# VistelV3.net
KiCad netlist of a schematic drawn in EAGLE
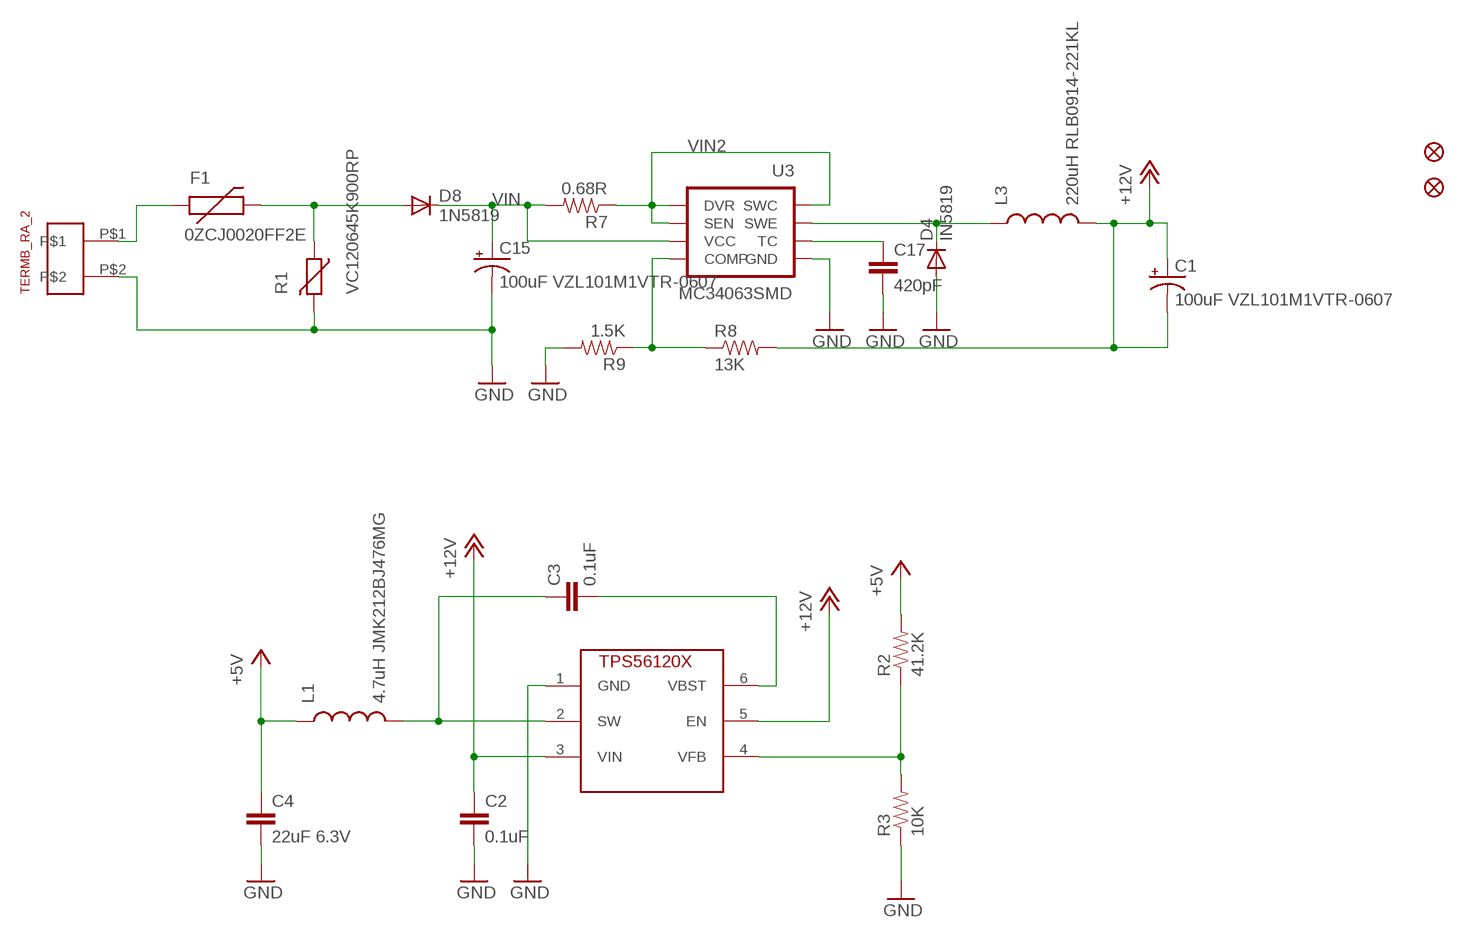
[diagram p0: schematic, sheet 1]
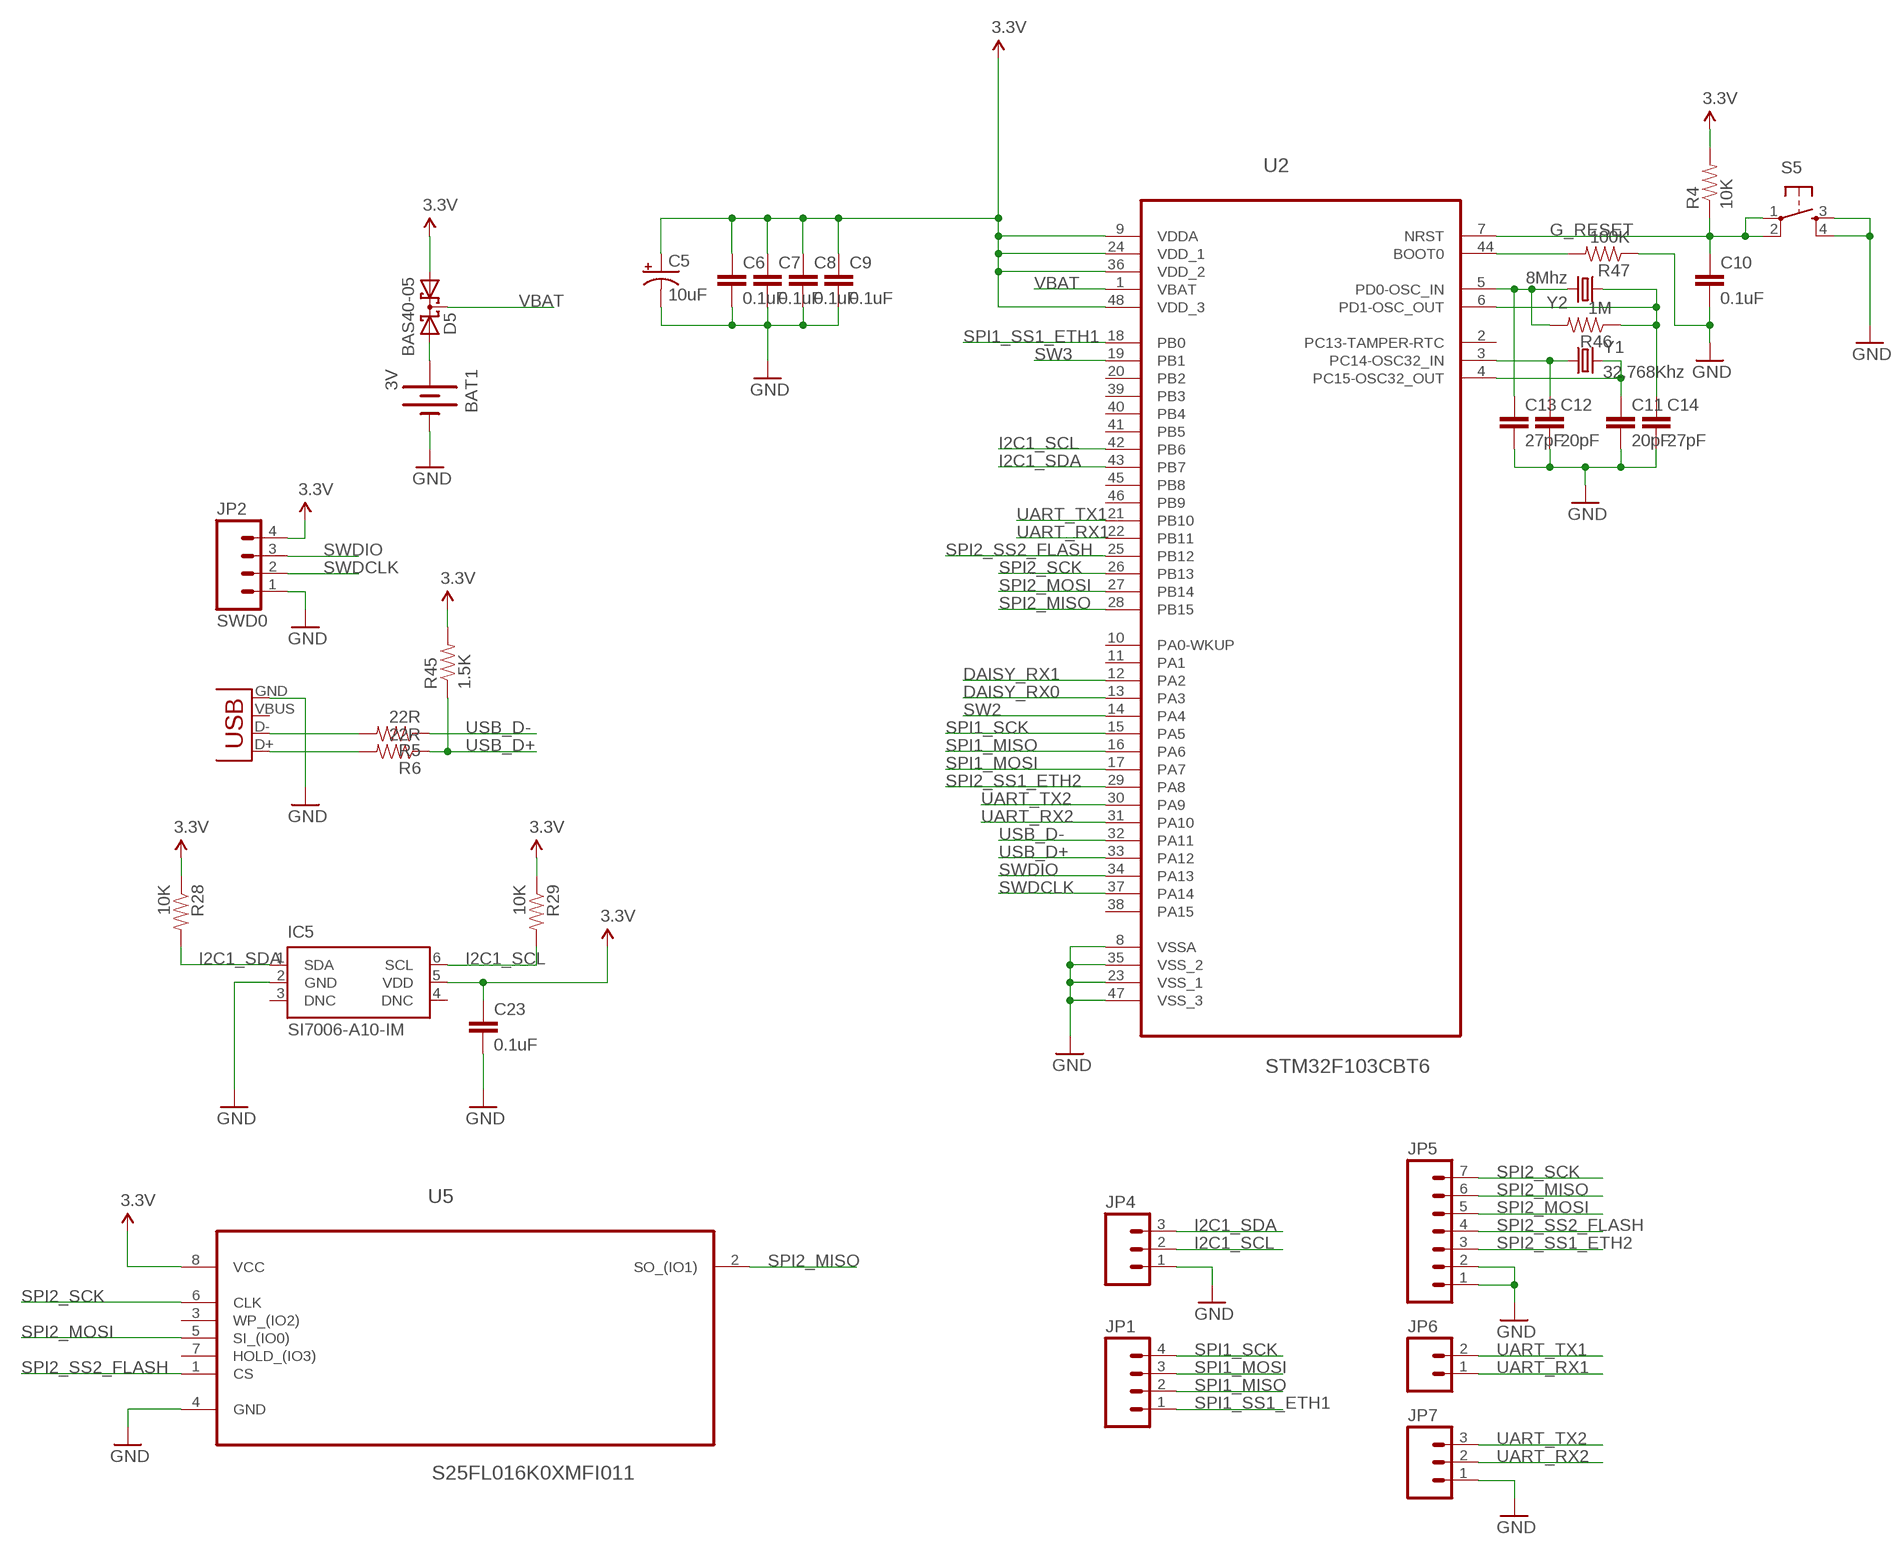
[diagram p1: schematic, sheet 2]
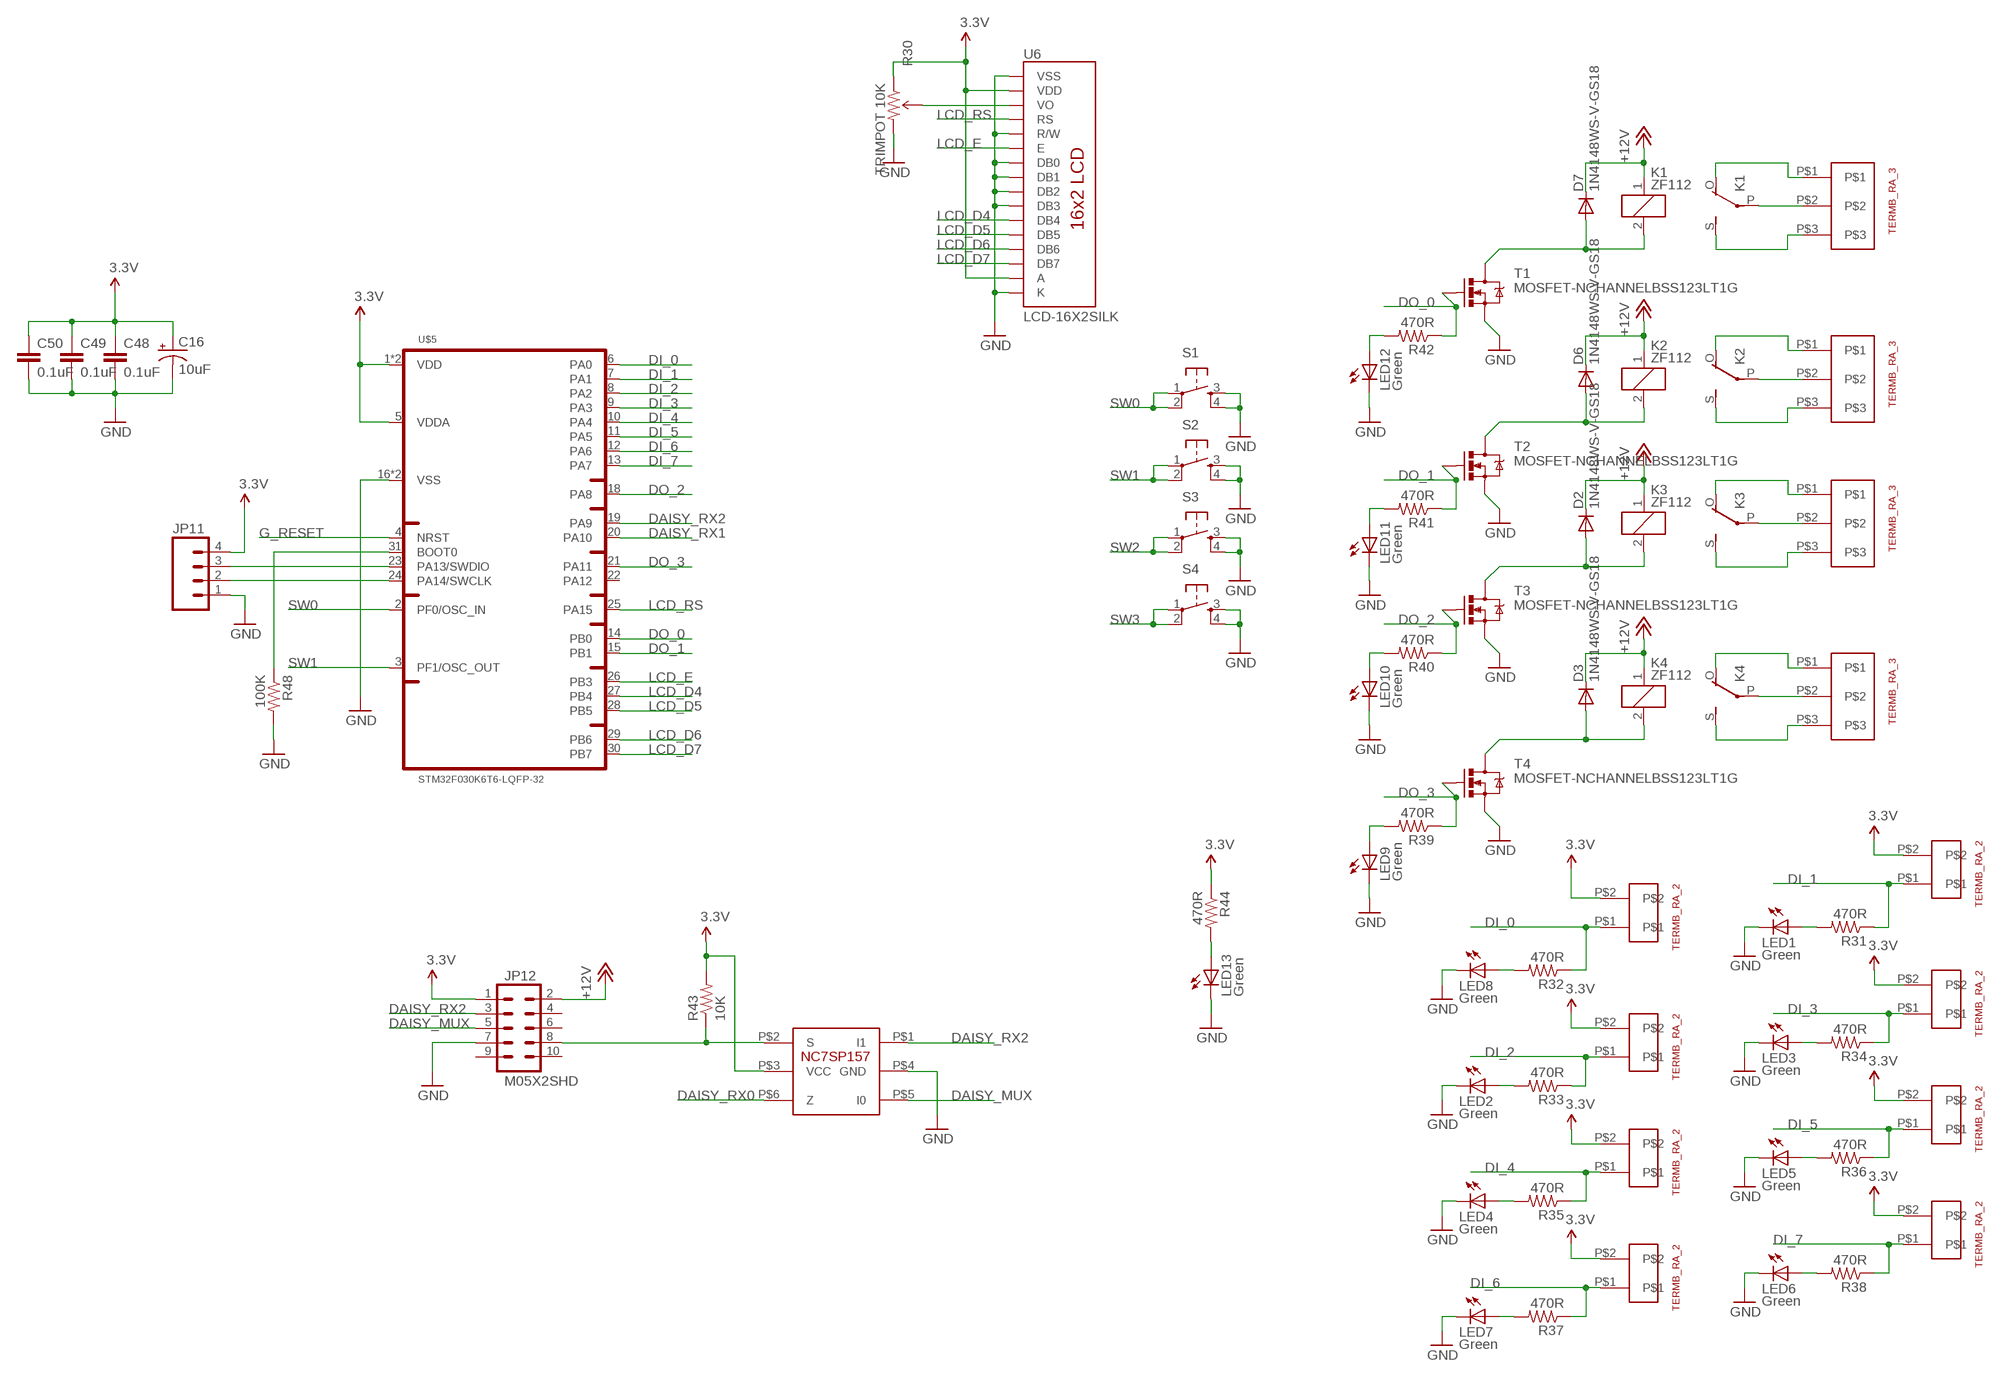
[diagram p2: schematic, sheet 3]
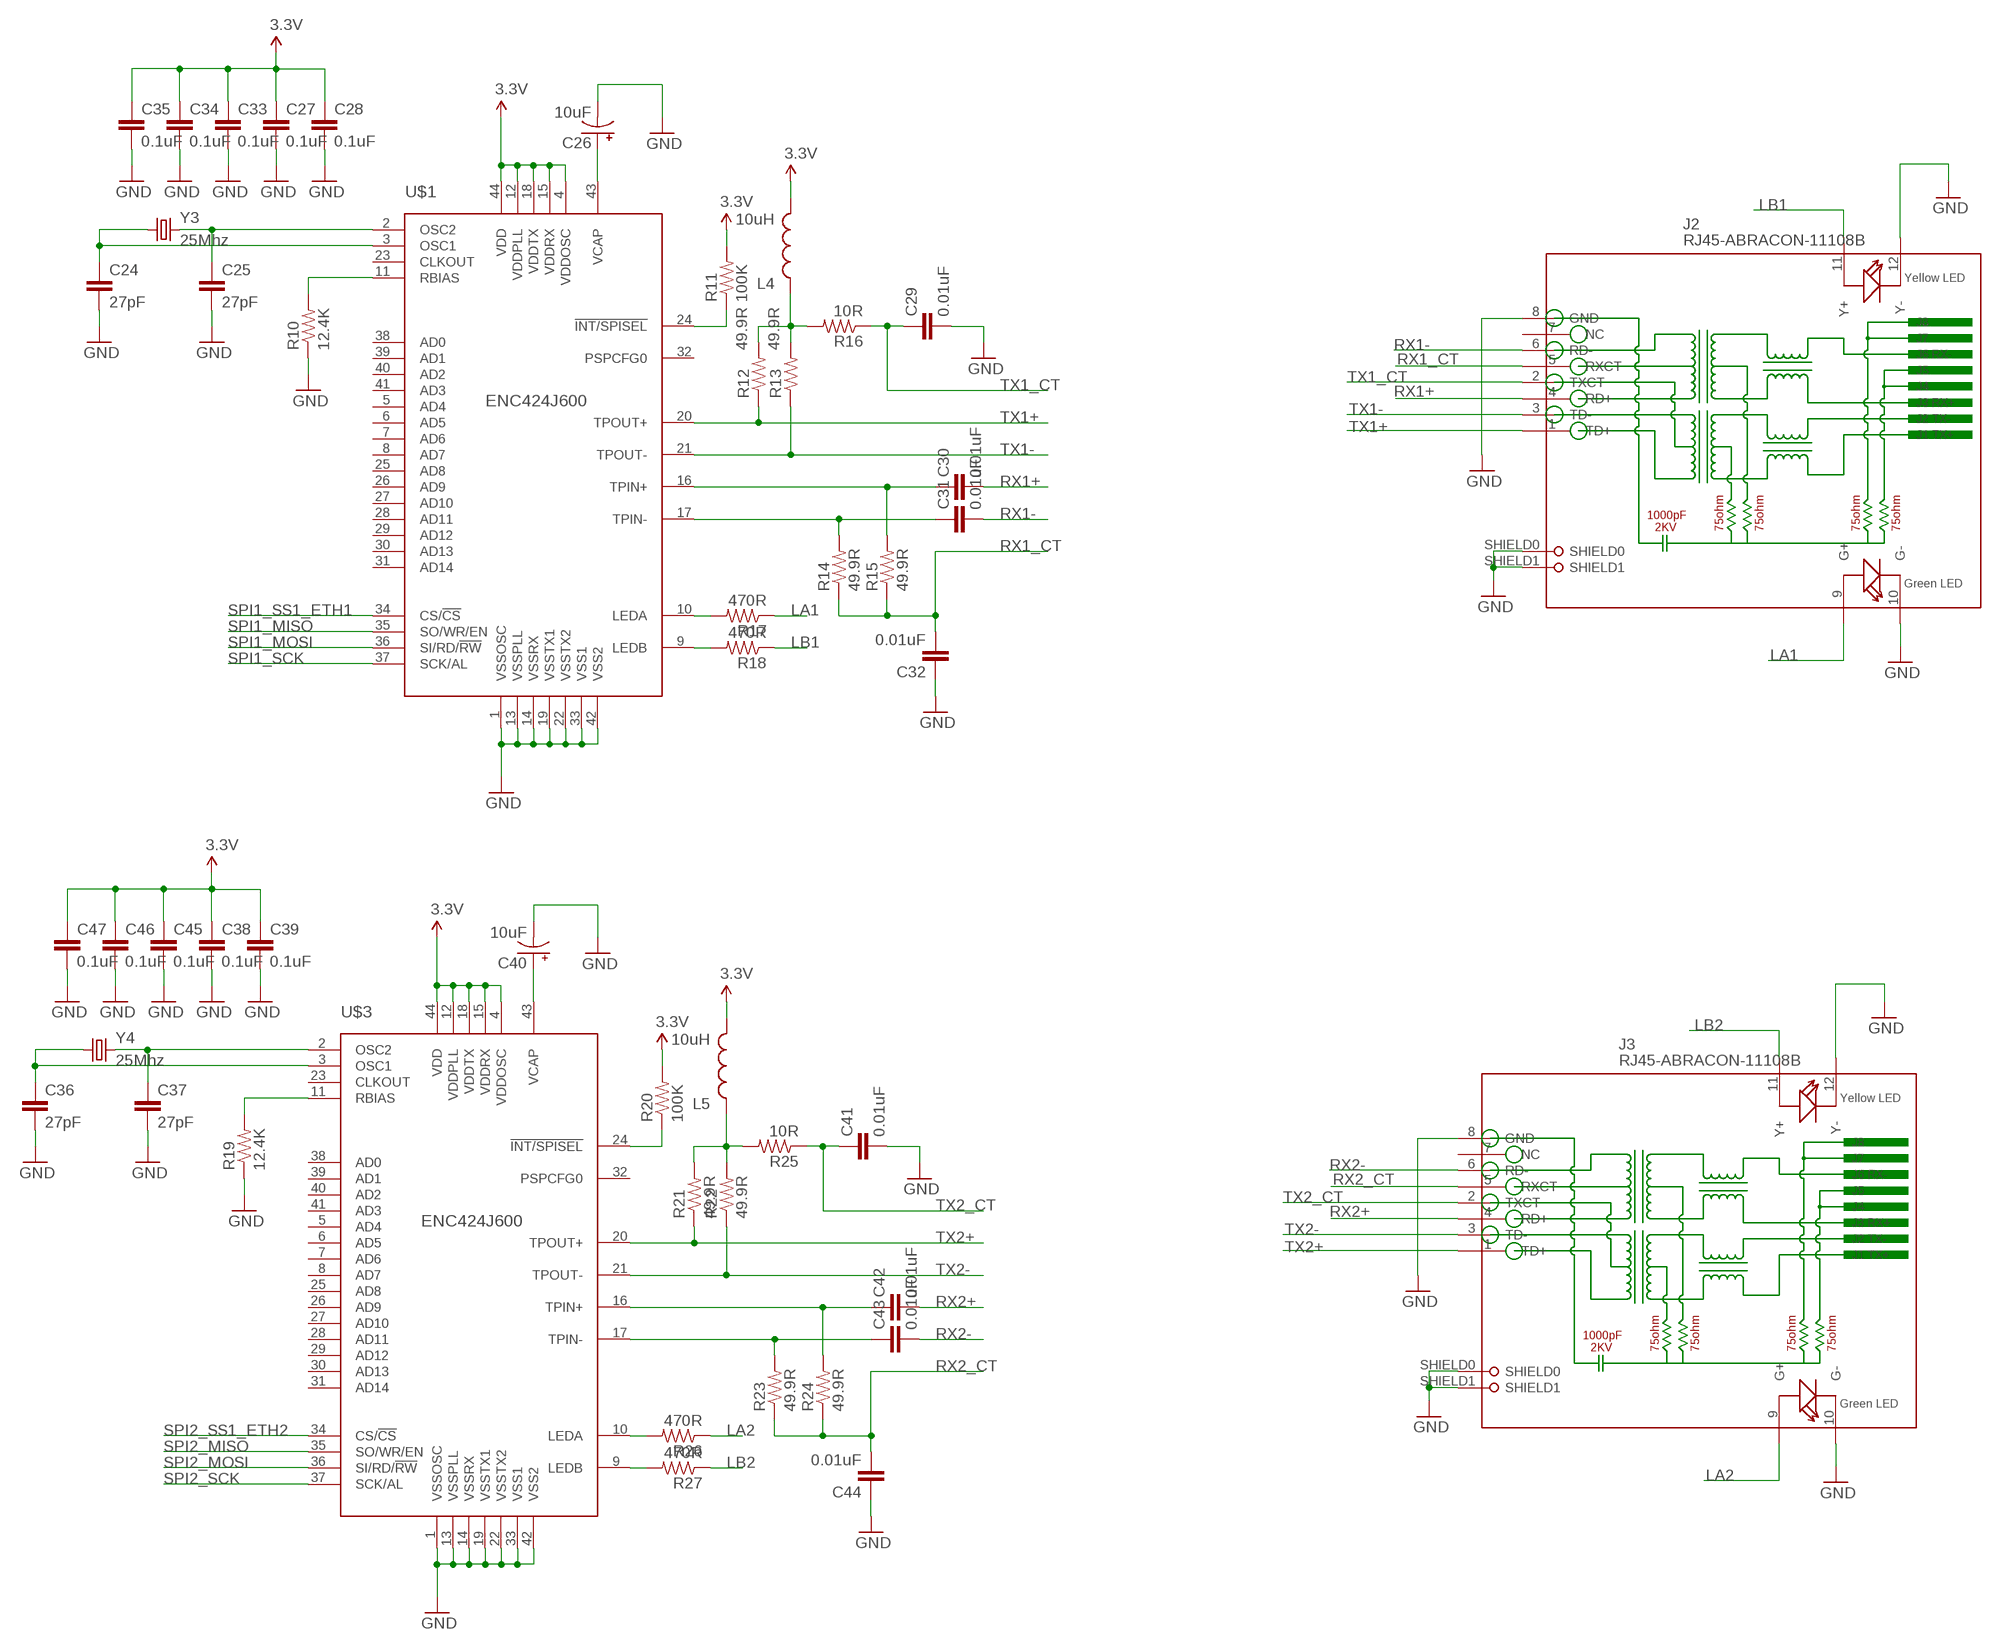
[diagram p3: schematic, sheet 4]
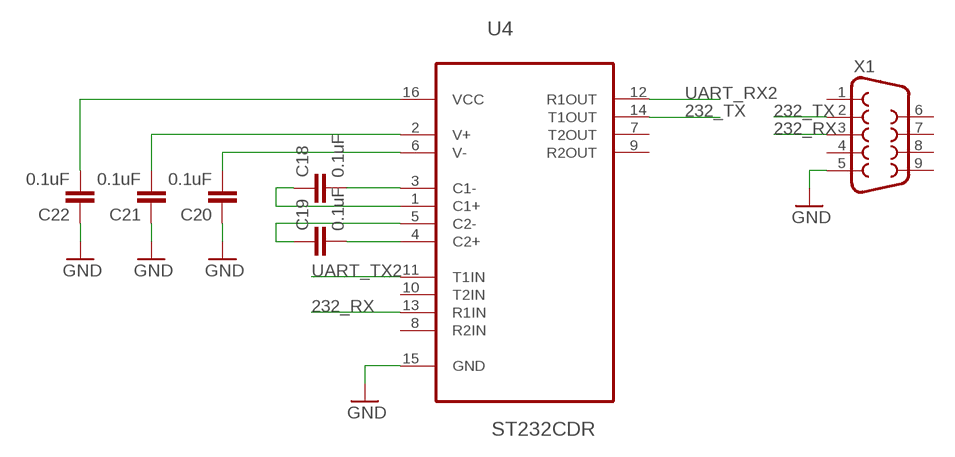
[diagram p4: schematic, sheet 5]

(export (version "E")
  (design (tool "Eeschema 10.0.6"))
  (components
    (comp (ref "BAT1")
      (value "3V")
      (footprint "eagle-import:BATTCOM_20MM_PTH")
      (libsource (lib "eagle-import") (part "BATTERY20PTH"))
    )
    (comp (ref "C5")
      (value "10uF")
      (footprint "eagle-import:EIA3216")
      (libsource (lib "eagle-import") (part "10UF-TANT"))
    )
    (comp (ref "C6")
      (value "0.1uF")
      (footprint "eagle-import:0805")
      (libsource (lib "eagle-import") (part "CAP0805"))
    )
    (comp (ref "C7")
      (value "0.1uF")
      (footprint "eagle-import:0805")
      (libsource (lib "eagle-import") (part "CAP0805"))
    )
    (comp (ref "C8")
      (value "0.1uF")
      (footprint "eagle-import:0805")
      (libsource (lib "eagle-import") (part "CAP0805"))
    )
    (comp (ref "C9")
      (value "0.1uF")
      (footprint "eagle-import:0805")
      (libsource (lib "eagle-import") (part "CAP0805"))
    )
    (comp (ref "C10")
      (value "0.1uF")
      (footprint "eagle-import:0805")
      (libsource (lib "eagle-import") (part "CAP0805"))
    )
    (comp (ref "C11")
      (value "20pF")
      (footprint "eagle-import:0805")
      (libsource (lib "eagle-import") (part "CAP0805"))
    )
    (comp (ref "C12")
      (value "20pF")
      (footprint "eagle-import:0805")
      (libsource (lib "eagle-import") (part "CAP0805"))
    )
    (comp (ref "C13")
      (value "27pF")
      (footprint "eagle-import:0805")
      (libsource (lib "eagle-import") (part "CAP0805"))
    )
    (comp (ref "C14")
      (value "27pF")
      (footprint "eagle-import:0805")
      (libsource (lib "eagle-import") (part "CAP0805"))
    )
    (comp (ref "C23")
      (value "0.1uF")
      (footprint "eagle-import:0805")
      (libsource (lib "eagle-import") (part "CAP0805"))
    )
    (comp (ref "D5")
      (value "BAS40-05")
      (footprint "eagle-import:SOT23")
      (libsource (lib "eagle-import") (part "BAS40-05"))
    )
    (comp (ref "IC5")
      (value "SI7006-A10-IM")
      (footprint "eagle-import:DFN6-3X3")
      (fields (field (name "MF") "Silicon Labs") (field (name "MPN") "Si7006-A10-IM"))
      (libsource (lib "eagle-import") (part "SI7006-A10-IM"))
    )
    (comp (ref "JP1")
      (value "M04PTH")
      (footprint "eagle-import:1X04")
      (libsource (lib "eagle-import") (part "M04PTH"))
    )
    (comp (ref "JP2")
      (value "SWD0")
      (footprint "eagle-import:1X04")
      (libsource (lib "eagle-import") (part "M04PTH"))
    )
    (comp (ref "JP3")
      (value "USB-B")
      (footprint "eagle-import:USB-B-PTH")
      (libsource (lib "eagle-import") (part "USBPTH"))
    )
    (comp (ref "JP4")
      (value "M03PTH")
      (footprint "eagle-import:1X03")
      (libsource (lib "eagle-import") (part "M03PTH"))
    )
    (comp (ref "JP5")
      (value "M07")
      (footprint "eagle-import:1X07")
      (libsource (lib "eagle-import") (part "M07"))
    )
    (comp (ref "JP6")
      (value "M02PTH")
      (footprint "eagle-import:1X02")
      (libsource (lib "eagle-import") (part "M02PTH"))
    )
    (comp (ref "JP7")
      (value "M03PTH")
      (footprint "eagle-import:1X03")
      (libsource (lib "eagle-import") (part "M03PTH"))
    )
    (comp (ref "R4")
      (value "10K")
      (footprint "eagle-import:0805")
      (libsource (lib "eagle-import") (part "SparkFun-Resistors_RESISTOR0805-RES"))
    )
    (comp (ref "R5")
      (value "22R")
      (footprint "eagle-import:0805")
      (libsource (lib "eagle-import") (part "SparkFun-Resistors_RESISTOR0805-RES"))
    )
    (comp (ref "R6")
      (value "22R")
      (footprint "eagle-import:0805")
      (libsource (lib "eagle-import") (part "SparkFun-Resistors_RESISTOR0805-RES"))
    )
    (comp (ref "R28")
      (value "10K")
      (footprint "eagle-import:0805")
      (libsource (lib "eagle-import") (part "SparkFun-Resistors_RESISTOR0805-RES"))
    )
    (comp (ref "R29")
      (value "10K")
      (footprint "eagle-import:0805")
      (libsource (lib "eagle-import") (part "SparkFun-Resistors_RESISTOR0805-RES"))
    )
    (comp (ref "R45")
      (value "1.5K")
      (footprint "eagle-import:0805")
      (libsource (lib "eagle-import") (part "SparkFun-Resistors_RESISTOR0805-RES"))
    )
    (comp (ref "R46")
      (value "1M")
      (footprint "eagle-import:0805")
      (libsource (lib "eagle-import") (part "SparkFun-Resistors_RESISTOR0805-RES"))
    )
    (comp (ref "R47")
      (value "100K")
      (footprint "eagle-import:0805")
      (libsource (lib "eagle-import") (part "SparkFun-Resistors_RESISTOR0805-RES"))
    )
    (comp (ref "S5")
      (value "TAC_SWITCHPTH")
      (footprint "eagle-import:TACTILE-PTH")
      (libsource (lib "eagle-import") (part "TAC_SWITCHPTH"))
    )
    (comp (ref "U2")
      (value "STM32F103CBT6")
      (footprint "eagle-import:QFP50P900X900X160-48N")
      (libsource (lib "eagle-import") (part "STM32F103CBT6"))
    )
    (comp (ref "U5")
      (value "S25FL016K0XMFI011")
      (footprint "eagle-import:SOIC127P800X215-8N")
      (libsource (lib "eagle-import") (part "S25FL016K0XMFI011"))
    )
    (comp (ref "Y1")
      (value "32.768Khz")
      (footprint "eagle-import:MC-306")
      (fields (field (name "MPN") "MC-306 60.0KHZ  100PPM ,12.5PF"))
      (libsource (lib "eagle-import") (part "MC-306"))
    )
    (comp (ref "Y2")
      (value "8Mhz")
      (footprint "eagle-import:HC49US")
      (libsource (lib "eagle-import") (part "CRYSTALHC49US"))
    )
    (comp (ref "C24")
      (value "27pF")
      (footprint "eagle-import:0805")
      (libsource (lib "eagle-import") (part "CAP0805"))
    )
    (comp (ref "C25")
      (value "27pF")
      (footprint "eagle-import:0805")
      (libsource (lib "eagle-import") (part "CAP0805"))
    )
    (comp (ref "C26")
      (value "10uF")
      (footprint "eagle-import:EIA3528-KIT")
      (libsource (lib "eagle-import") (part "CAP_POL3528-KIT"))
    )
    (comp (ref "C27")
      (value "0.1uF")
      (footprint "eagle-import:0805")
      (libsource (lib "eagle-import") (part "CAP0805"))
    )
    (comp (ref "C28")
      (value "0.1uF")
      (footprint "eagle-import:0805")
      (libsource (lib "eagle-import") (part "CAP0805"))
    )
    (comp (ref "C29")
      (value "0.01uF")
      (footprint "eagle-import:0805")
      (libsource (lib "eagle-import") (part "CAP0805"))
    )
    (comp (ref "C30")
      (value "0.01uF")
      (footprint "eagle-import:0805")
      (libsource (lib "eagle-import") (part "CAP0805"))
    )
    (comp (ref "C31")
      (value "0.01uF")
      (footprint "eagle-import:0805")
      (libsource (lib "eagle-import") (part "CAP0805"))
    )
    (comp (ref "C32")
      (value "0.01uF")
      (footprint "eagle-import:0805")
      (libsource (lib "eagle-import") (part "CAP0805"))
    )
    (comp (ref "C33")
      (value "0.1uF")
      (footprint "eagle-import:0805")
      (libsource (lib "eagle-import") (part "CAP0805"))
    )
    (comp (ref "C34")
      (value "0.1uF")
      (footprint "eagle-import:0805")
      (libsource (lib "eagle-import") (part "CAP0805"))
    )
    (comp (ref "C35")
      (value "0.1uF")
      (footprint "eagle-import:0805")
      (libsource (lib "eagle-import") (part "CAP0805"))
    )
    (comp (ref "C36")
      (value "27pF")
      (footprint "eagle-import:0805")
      (libsource (lib "eagle-import") (part "CAP0805"))
    )
    (comp (ref "C37")
      (value "27pF")
      (footprint "eagle-import:0805")
      (libsource (lib "eagle-import") (part "CAP0805"))
    )
    (comp (ref "C38")
      (value "0.1uF")
      (footprint "eagle-import:0805")
      (libsource (lib "eagle-import") (part "CAP0805"))
    )
    (comp (ref "C39")
      (value "0.1uF")
      (footprint "eagle-import:0805")
      (libsource (lib "eagle-import") (part "CAP0805"))
    )
    (comp (ref "C40")
      (value "10uF")
      (footprint "eagle-import:EIA3528-KIT")
      (libsource (lib "eagle-import") (part "CAP_POL3528-KIT"))
    )
    (comp (ref "C41")
      (value "0.01uF")
      (footprint "eagle-import:0805")
      (libsource (lib "eagle-import") (part "CAP0805"))
    )
    (comp (ref "C42")
      (value "0.01uF")
      (footprint "eagle-import:0805")
      (libsource (lib "eagle-import") (part "CAP0805"))
    )
    (comp (ref "C43")
      (value "0.01uF")
      (footprint "eagle-import:0805")
      (libsource (lib "eagle-import") (part "CAP0805"))
    )
    (comp (ref "C44")
      (value "0.01uF")
      (footprint "eagle-import:0805")
      (libsource (lib "eagle-import") (part "CAP0805"))
    )
    (comp (ref "C45")
      (value "0.1uF")
      (footprint "eagle-import:0805")
      (libsource (lib "eagle-import") (part "CAP0805"))
    )
    (comp (ref "C46")
      (value "0.1uF")
      (footprint "eagle-import:0805")
      (libsource (lib "eagle-import") (part "CAP0805"))
    )
    (comp (ref "C47")
      (value "0.1uF")
      (footprint "eagle-import:0805")
      (libsource (lib "eagle-import") (part "CAP0805"))
    )
    (comp (ref "J2")
      (value "RJ45-ABRACON-11108B")
      (footprint "eagle-import:RJ45-ABRACON-111008B")
      (libsource (lib "eagle-import") (part "RJ45-ABRACON-11108B"))
    )
    (comp (ref "J3")
      (value "RJ45-ABRACON-11108B")
      (footprint "eagle-import:RJ45-ABRACON-111008B")
      (libsource (lib "eagle-import") (part "RJ45-ABRACON-11108B"))
    )
    (comp (ref "L4")
      (value "10uH")
      (footprint "eagle-import:0805")
      (libsource (lib "eagle-import") (part "INDUCTOR0805"))
    )
    (comp (ref "L5")
      (value "10uH")
      (footprint "eagle-import:0805")
      (libsource (lib "eagle-import") (part "INDUCTOR0805"))
    )
    (comp (ref "R10")
      (value "12.4K")
      (footprint "eagle-import:0805")
      (libsource (lib "eagle-import") (part "SparkFun-Resistors_RESISTOR0805-RES"))
    )
    (comp (ref "R11")
      (value "100K")
      (footprint "eagle-import:0805")
      (libsource (lib "eagle-import") (part "SparkFun-Resistors_RESISTOR0805-RES"))
    )
    (comp (ref "R12")
      (value "49.9R")
      (footprint "eagle-import:0805")
      (libsource (lib "eagle-import") (part "SparkFun-Resistors_RESISTOR0805-RES"))
    )
    (comp (ref "R13")
      (value "49.9R")
      (footprint "eagle-import:0805")
      (libsource (lib "eagle-import") (part "SparkFun-Resistors_RESISTOR0805-RES"))
    )
    (comp (ref "R14")
      (value "49.9R")
      (footprint "eagle-import:0805")
      (libsource (lib "eagle-import") (part "SparkFun-Resistors_RESISTOR0805-RES"))
    )
    (comp (ref "R15")
      (value "49.9R")
      (footprint "eagle-import:0805")
      (libsource (lib "eagle-import") (part "SparkFun-Resistors_RESISTOR0805-RES"))
    )
    (comp (ref "R16")
      (value "10R")
      (footprint "eagle-import:0805")
      (libsource (lib "eagle-import") (part "SparkFun-Resistors_RESISTOR0805-RES"))
    )
    (comp (ref "R17")
      (value "470R")
      (footprint "eagle-import:0805")
      (libsource (lib "eagle-import") (part "SparkFun-Resistors_RESISTOR0805-RES"))
    )
    (comp (ref "R18")
      (value "470R")
      (footprint "eagle-import:0805")
      (libsource (lib "eagle-import") (part "SparkFun-Resistors_RESISTOR0805-RES"))
    )
    (comp (ref "R19")
      (value "12.4K")
      (footprint "eagle-import:0805")
      (libsource (lib "eagle-import") (part "SparkFun-Resistors_RESISTOR0805-RES"))
    )
    (comp (ref "R20")
      (value "100K")
      (footprint "eagle-import:0805")
      (libsource (lib "eagle-import") (part "SparkFun-Resistors_RESISTOR0805-RES"))
    )
    (comp (ref "R21")
      (value "49.9R")
      (footprint "eagle-import:0805")
      (libsource (lib "eagle-import") (part "SparkFun-Resistors_RESISTOR0805-RES"))
    )
    (comp (ref "R22")
      (value "49.9R")
      (footprint "eagle-import:0805")
      (libsource (lib "eagle-import") (part "SparkFun-Resistors_RESISTOR0805-RES"))
    )
    (comp (ref "R23")
      (value "49.9R")
      (footprint "eagle-import:0805")
      (libsource (lib "eagle-import") (part "SparkFun-Resistors_RESISTOR0805-RES"))
    )
    (comp (ref "R24")
      (value "49.9R")
      (footprint "eagle-import:0805")
      (libsource (lib "eagle-import") (part "SparkFun-Resistors_RESISTOR0805-RES"))
    )
    (comp (ref "R25")
      (value "10R")
      (footprint "eagle-import:0805")
      (libsource (lib "eagle-import") (part "SparkFun-Resistors_RESISTOR0805-RES"))
    )
    (comp (ref "R26")
      (value "470R")
      (footprint "eagle-import:0805")
      (libsource (lib "eagle-import") (part "SparkFun-Resistors_RESISTOR0805-RES"))
    )
    (comp (ref "R27")
      (value "470R")
      (footprint "eagle-import:0805")
      (libsource (lib "eagle-import") (part "SparkFun-Resistors_RESISTOR0805-RES"))
    )
    (comp (ref "U$1")
      (value "ENC424J600")
      (footprint "eagle-import:TQFP-44")
      (libsource (lib "eagle-import") (part "ENC424J600"))
    )
    (comp (ref "U$3")
      (value "ENC424J600")
      (footprint "eagle-import:TQFP-44")
      (libsource (lib "eagle-import") (part "ENC424J600"))
    )
    (comp (ref "Y3")
      (value "25Mhz")
      (footprint "eagle-import:CRYSTAL-SMD-10.5X4.8-2PIN")
      (libsource (lib "eagle-import") (part "CRYSTAL10.5X4.8"))
    )
    (comp (ref "Y4")
      (value "25Mhz")
      (footprint "eagle-import:CRYSTAL-SMD-10.5X4.8-2PIN")
      (libsource (lib "eagle-import") (part "CRYSTAL10.5X4.8"))
    )
    (comp (ref "C18")
      (value "0.1uF")
      (footprint "eagle-import:0805")
      (libsource (lib "eagle-import") (part "SparkFun-Passives_CAP0805"))
    )
    (comp (ref "C19")
      (value "0.1uF")
      (footprint "eagle-import:0805")
      (libsource (lib "eagle-import") (part "SparkFun-Passives_CAP0805"))
    )
    (comp (ref "C20")
      (value "0.1uF")
      (footprint "eagle-import:0805")
      (libsource (lib "eagle-import") (part "SparkFun-Passives_CAP0805"))
    )
    (comp (ref "C21")
      (value "0.1uF")
      (footprint "eagle-import:0805")
      (libsource (lib "eagle-import") (part "SparkFun-Passives_CAP0805"))
    )
    (comp (ref "C22")
      (value "0.1uF")
      (footprint "eagle-import:0805")
      (libsource (lib "eagle-import") (part "SparkFun-Passives_CAP0805"))
    )
    (comp (ref "U4")
      (value "ST232CDR")
      (footprint "eagle-import:SOIC127P600X175-16N")
      (libsource (lib "eagle-import") (part "ST232CDR"))
    )
    (comp (ref "X1")
      (value "DB9FEMALE")
      (footprint "eagle-import:DB9")
      (libsource (lib "eagle-import") (part "DB9FEMALE"))
    )
    (comp (ref "C1")
      (value "100uF VZL101M1VTR-0607")
      (footprint "eagle-import:PANASONIC_D")
      (libsource (lib "eagle-import") (part "CAP_POLD"))
    )
    (comp (ref "C2")
      (value "0.1uF")
      (footprint "eagle-import:0805")
      (libsource (lib "eagle-import") (part "SparkFun-Passives_CAP0805"))
    )
    (comp (ref "C3")
      (value "0.1uF")
      (footprint "eagle-import:0805")
      (libsource (lib "eagle-import") (part "SparkFun-Passives_CAP0805"))
    )
    (comp (ref "C4")
      (value "22uF 6.3V")
      (footprint "eagle-import:0805")
      (libsource (lib "eagle-import") (part "SparkFun-Passives_CAP0805"))
    )
    (comp (ref "C15")
      (value "100uF VZL101M1VTR-0607")
      (footprint "eagle-import:PANASONIC_D")
      (libsource (lib "eagle-import") (part "CAP_POLD"))
    )
    (comp (ref "C17")
      (value "420pF")
      (footprint "eagle-import:0805")
      (libsource (lib "eagle-import") (part "SparkFun-Passives_CAP0805"))
    )
    (comp (ref "D4")
      (value "IN5819")
      (footprint "eagle-import:SMA-DIODE")
      (libsource (lib "eagle-import") (part "DIODESMA"))
    )
    (comp (ref "D8")
      (value "1N5819")
      (footprint "eagle-import:SMB-DIODE")
      (libsource (lib "eagle-import") (part "DIODESMB"))
    )
    (comp (ref "F1")
      (value "0ZCJ0020FF2E")
      (footprint "eagle-import:PTC-1206")
      (libsource (lib "eagle-import") (part "PTCSMD"))
    )
    (comp (ref "FID1")
      (value "FIDUCIAL1.5X3")
      (footprint "eagle-import:FIDUCIAL-1.5X3")
      (libsource (lib "eagle-import") (part "FIDUCIAL1.5X3"))
    )
    (comp (ref "FID2")
      (value "FIDUCIAL1.5X3")
      (footprint "eagle-import:FIDUCIAL-1.5X3")
      (libsource (lib "eagle-import") (part "FIDUCIAL1.5X3"))
    )
    (comp (ref "L1")
      (value "4.7uH JMK212BJ476MG")
      (footprint "eagle-import:0805")
      (libsource (lib "eagle-import") (part "INDUCTOR0805"))
    )
    (comp (ref "L3")
      (value "220uH RLB0914-221KL")
      (footprint "eagle-import:CDRH125")
      (libsource (lib "eagle-import") (part "INDUCTORPWR"))
    )
    (comp (ref "R1")
      (value "VC120645K900RP")
      (footprint "eagle-import:CT_CN1206")
      (libsource (lib "eagle-import") (part "VARISTORCN1206"))
    )
    (comp (ref "R2")
      (value "41.2K")
      (footprint "eagle-import:0805")
      (libsource (lib "eagle-import") (part "RESISTOR0805-RES"))
    )
    (comp (ref "R3")
      (value "10K")
      (footprint "eagle-import:0805")
      (libsource (lib "eagle-import") (part "RESISTOR0805-RES"))
    )
    (comp (ref "R7")
      (value "0.68R")
      (footprint "eagle-import:0805")
      (libsource (lib "eagle-import") (part "RESISTOR0805-RES"))
    )
    (comp (ref "R8")
      (value "13K")
      (footprint "eagle-import:0805")
      (libsource (lib "eagle-import") (part "RESISTOR0805-RES"))
    )
    (comp (ref "R9")
      (value "1.5K")
      (footprint "eagle-import:0805")
      (libsource (lib "eagle-import") (part "RESISTOR0805-RES"))
    )
    (comp (ref "U$2")
      (value "1X02_TERMB_RA")
      (footprint "eagle-import:1X02_TERMB_RA")
      (libsource (lib "eagle-import") (part "1X02_TERMB_RA"))
    )
    (comp (ref "U$18")
      (value "TPS56120X")
      (footprint "eagle-import:TSOT23-6_DDC")
      (libsource (lib "eagle-import") (part "TPS56120X"))
    )
    (comp (ref "U3")
      (value "MC34063SMD")
      (footprint "eagle-import:SO08")
      (libsource (lib "eagle-import") (part "MC34063SMD"))
    )
    (comp (ref "C16")
      (value "10uF")
      (footprint "eagle-import:EIA3216")
      (libsource (lib "eagle-import") (part "10UF-TANT"))
    )
    (comp (ref "C48")
      (value "0.1uF")
      (footprint "eagle-import:0805")
      (libsource (lib "eagle-import") (part "CAP0805"))
    )
    (comp (ref "C49")
      (value "0.1uF")
      (footprint "eagle-import:0805")
      (libsource (lib "eagle-import") (part "CAP0805"))
    )
    (comp (ref "C50")
      (value "0.1uF")
      (footprint "eagle-import:0805")
      (libsource (lib "eagle-import") (part "CAP0805"))
    )
    (comp (ref "D2")
      (value "1N4148WS-V-GS18")
      (footprint "eagle-import:SMA-DIODE_ALT")
      (libsource (lib "eagle-import") (part "DIODESMA-ALT"))
    )
    (comp (ref "D3")
      (value "1N4148WS-V-GS18")
      (footprint "eagle-import:SMA-DIODE_ALT")
      (libsource (lib "eagle-import") (part "DIODESMA-ALT"))
    )
    (comp (ref "D6")
      (value "1N4148WS-V-GS18")
      (footprint "eagle-import:SMA-DIODE_ALT")
      (libsource (lib "eagle-import") (part "DIODESMA-ALT"))
    )
    (comp (ref "D7")
      (value "1N4148WS-V-GS18")
      (footprint "eagle-import:SMA-DIODE_ALT")
      (libsource (lib "eagle-import") (part "DIODESMA-ALT"))
    )
    (comp (ref "JP11")
      (value "M04PTH")
      (footprint "eagle-import:1X04")
      (libsource (lib "eagle-import") (part "M04PTH"))
    )
    (comp (ref "JP12")
      (value "M05X2SHD")
      (footprint "eagle-import:2X5-SHROUDED")
      (libsource (lib "eagle-import") (part "M05X2SHD"))
    )
    (comp (ref "K1")
      (value "ZF112")
      (footprint "eagle-import:ZF112")
      (libsource (lib "eagle-import") (part "ZF112"))
    )
    (comp (ref "K2")
      (value "ZF112")
      (footprint "eagle-import:ZF112")
      (libsource (lib "eagle-import") (part "ZF112"))
    )
    (comp (ref "K3")
      (value "ZF112")
      (footprint "eagle-import:ZF112")
      (libsource (lib "eagle-import") (part "ZF112"))
    )
    (comp (ref "K4")
      (value "ZF112")
      (footprint "eagle-import:ZF112")
      (libsource (lib "eagle-import") (part "ZF112"))
    )
    (comp (ref "LED1")
      (value "Green")
      (footprint "eagle-import:LED-1206")
      (libsource (lib "eagle-import") (part "LED1206"))
    )
    (comp (ref "LED2")
      (value "Green")
      (footprint "eagle-import:LED-1206")
      (libsource (lib "eagle-import") (part "LED1206"))
    )
    (comp (ref "LED3")
      (value "Green")
      (footprint "eagle-import:LED-1206")
      (libsource (lib "eagle-import") (part "LED1206"))
    )
    (comp (ref "LED4")
      (value "Green")
      (footprint "eagle-import:LED-1206")
      (libsource (lib "eagle-import") (part "LED1206"))
    )
    (comp (ref "LED5")
      (value "Green")
      (footprint "eagle-import:LED-1206")
      (libsource (lib "eagle-import") (part "LED1206"))
    )
    (comp (ref "LED6")
      (value "Green")
      (footprint "eagle-import:LED-1206")
      (libsource (lib "eagle-import") (part "LED1206"))
    )
    (comp (ref "LED7")
      (value "Green")
      (footprint "eagle-import:LED-1206")
      (libsource (lib "eagle-import") (part "LED1206"))
    )
    (comp (ref "LED8")
      (value "Green")
      (footprint "eagle-import:LED-1206")
      (libsource (lib "eagle-import") (part "LED1206"))
    )
    (comp (ref "LED9")
      (value "Green")
      (footprint "eagle-import:LED-1206")
      (libsource (lib "eagle-import") (part "LED1206"))
    )
    (comp (ref "LED10")
      (value "Green")
      (footprint "eagle-import:LED-1206")
      (libsource (lib "eagle-import") (part "LED1206"))
    )
    (comp (ref "LED11")
      (value "Green")
      (footprint "eagle-import:LED-1206")
      (libsource (lib "eagle-import") (part "LED1206"))
    )
    (comp (ref "LED12")
      (value "Green")
      (footprint "eagle-import:LED-1206")
      (libsource (lib "eagle-import") (part "LED1206"))
    )
    (comp (ref "LED13")
      (value "Green")
      (footprint "eagle-import:LED-1206")
      (libsource (lib "eagle-import") (part "LED1206"))
    )
    (comp (ref "R30")
      (value "TRIMPOT 10K")
      (footprint "eagle-import:TRIM_POT_PTH")
      (libsource (lib "eagle-import") (part "TRIMPOTPTH"))
    )
    (comp (ref "R31")
      (value "470R")
      (footprint "eagle-import:0805")
      (libsource (lib "eagle-import") (part "RESISTOR0805-RES"))
    )
    (comp (ref "R32")
      (value "470R")
      (footprint "eagle-import:0805")
      (libsource (lib "eagle-import") (part "RESISTOR0805-RES"))
    )
    (comp (ref "R33")
      (value "470R")
      (footprint "eagle-import:0805")
      (libsource (lib "eagle-import") (part "RESISTOR0805-RES"))
    )
    (comp (ref "R34")
      (value "470R")
      (footprint "eagle-import:0805")
      (libsource (lib "eagle-import") (part "RESISTOR0805-RES"))
    )
    (comp (ref "R35")
      (value "470R")
      (footprint "eagle-import:0805")
      (libsource (lib "eagle-import") (part "RESISTOR0805-RES"))
    )
    (comp (ref "R36")
      (value "470R")
      (footprint "eagle-import:0805")
      (libsource (lib "eagle-import") (part "RESISTOR0805-RES"))
    )
    (comp (ref "R37")
      (value "470R")
      (footprint "eagle-import:0805")
      (libsource (lib "eagle-import") (part "RESISTOR0805-RES"))
    )
    (comp (ref "R38")
      (value "470R")
      (footprint "eagle-import:0805")
      (libsource (lib "eagle-import") (part "RESISTOR0805-RES"))
    )
    (comp (ref "R39")
      (value "470R")
      (footprint "eagle-import:0805")
      (libsource (lib "eagle-import") (part "RESISTOR0805-RES"))
    )
    (comp (ref "R40")
      (value "470R")
      (footprint "eagle-import:0805")
      (libsource (lib "eagle-import") (part "RESISTOR0805-RES"))
    )
    (comp (ref "R41")
      (value "470R")
      (footprint "eagle-import:0805")
      (libsource (lib "eagle-import") (part "RESISTOR0805-RES"))
    )
    (comp (ref "R42")
      (value "470R")
      (footprint "eagle-import:0805")
      (libsource (lib "eagle-import") (part "RESISTOR0805-RES"))
    )
    (comp (ref "R43")
      (value "10K")
      (footprint "eagle-import:0805")
      (libsource (lib "eagle-import") (part "RESISTOR0805-RES"))
    )
    (comp (ref "R44")
      (value "470R")
      (footprint "eagle-import:0805")
      (libsource (lib "eagle-import") (part "RESISTOR0805-RES"))
    )
    (comp (ref "R48")
      (value "100K")
      (footprint "eagle-import:0805")
      (libsource (lib "eagle-import") (part "RESISTOR0805-RES"))
    )
    (comp (ref "S1")
      (value "TAC_SWITCHPTH")
      (footprint "eagle-import:TACTILE-PTH")
      (libsource (lib "eagle-import") (part "TAC_SWITCHPTH"))
    )
    (comp (ref "S2")
      (value "TAC_SWITCHPTH")
      (footprint "eagle-import:TACTILE-PTH")
      (libsource (lib "eagle-import") (part "TAC_SWITCHPTH"))
    )
    (comp (ref "S3")
      (value "TAC_SWITCHPTH")
      (footprint "eagle-import:TACTILE-PTH")
      (libsource (lib "eagle-import") (part "TAC_SWITCHPTH"))
    )
    (comp (ref "S4")
      (value "TAC_SWITCHPTH")
      (footprint "eagle-import:TACTILE-PTH")
      (libsource (lib "eagle-import") (part "TAC_SWITCHPTH"))
    )
    (comp (ref "T1")
      (value "MOSFET-NCHANNELBSS123LT1G")
      (footprint "eagle-import:SOT23")
      (libsource (lib "eagle-import") (part "MOSFET-NCHANNELBSS123LT1G"))
    )
    (comp (ref "T2")
      (value "MOSFET-NCHANNELBSS123LT1G")
      (footprint "eagle-import:SOT23")
      (libsource (lib "eagle-import") (part "MOSFET-NCHANNELBSS123LT1G"))
    )
    (comp (ref "T3")
      (value "MOSFET-NCHANNELBSS123LT1G")
      (footprint "eagle-import:SOT23")
      (libsource (lib "eagle-import") (part "MOSFET-NCHANNELBSS123LT1G"))
    )
    (comp (ref "T4")
      (value "MOSFET-NCHANNELBSS123LT1G")
      (footprint "eagle-import:SOT23")
      (libsource (lib "eagle-import") (part "MOSFET-NCHANNELBSS123LT1G"))
    )
    (comp (ref "U$4")
      (value "NC7SP157")
      (footprint "eagle-import:SC70-6")
      (libsource (lib "eagle-import") (part "NC7SP157"))
    )
    (comp (ref "U$5")
      (value "STM32F030K6T6-LQFP-32")
      (footprint "eagle-import:LQFP-32")
      (libsource (lib "eagle-import") (part "STM32F030K6T6-LQFP-32"))
    )
    (comp (ref "U$6")
      (value "1X02_TERMB_RA")
      (footprint "eagle-import:1X02_TERMB_RA")
      (libsource (lib "eagle-import") (part "1X02_TERMB_RA"))
    )
    (comp (ref "U$7")
      (value "1X02_TERMB_RA")
      (footprint "eagle-import:1X02_TERMB_RA")
      (libsource (lib "eagle-import") (part "1X02_TERMB_RA"))
    )
    (comp (ref "U$8")
      (value "1X02_TERMB_RA")
      (footprint "eagle-import:1X02_TERMB_RA")
      (libsource (lib "eagle-import") (part "1X02_TERMB_RA"))
    )
    (comp (ref "U$9")
      (value "1X02_TERMB_RA")
      (footprint "eagle-import:1X02_TERMB_RA")
      (libsource (lib "eagle-import") (part "1X02_TERMB_RA"))
    )
    (comp (ref "U$10")
      (value "1X02_TERMB_RA")
      (footprint "eagle-import:1X02_TERMB_RA")
      (libsource (lib "eagle-import") (part "1X02_TERMB_RA"))
    )
    (comp (ref "U$11")
      (value "1X02_TERMB_RA")
      (footprint "eagle-import:1X02_TERMB_RA")
      (libsource (lib "eagle-import") (part "1X02_TERMB_RA"))
    )
    (comp (ref "U$12")
      (value "1X02_TERMB_RA")
      (footprint "eagle-import:1X02_TERMB_RA")
      (libsource (lib "eagle-import") (part "1X02_TERMB_RA"))
    )
    (comp (ref "U$13")
      (value "1X02_TERMB_RA")
      (footprint "eagle-import:1X02_TERMB_RA")
      (libsource (lib "eagle-import") (part "1X02_TERMB_RA"))
    )
    (comp (ref "U$14")
      (value "1X03_TERMB_RA")
      (footprint "eagle-import:1X03_TERMB_RA")
      (libsource (lib "eagle-import") (part "1X03_TERMB_RA"))
    )
    (comp (ref "U$15")
      (value "1X03_TERMB_RA")
      (footprint "eagle-import:1X03_TERMB_RA")
      (libsource (lib "eagle-import") (part "1X03_TERMB_RA"))
    )
    (comp (ref "U$16")
      (value "1X03_TERMB_RA")
      (footprint "eagle-import:1X03_TERMB_RA")
      (libsource (lib "eagle-import") (part "1X03_TERMB_RA"))
    )
    (comp (ref "U$17")
      (value "1X03_TERMB_RA")
      (footprint "eagle-import:1X03_TERMB_RA")
      (libsource (lib "eagle-import") (part "1X03_TERMB_RA"))
    )
    (comp (ref "U6")
      (value "LCD-16X2SILK")
      (footprint "eagle-import:LCD-16X2")
      (libsource (lib "eagle-import") (part "LCD-16X2SILK"))
    )
  )
  (nets
    (net (code "1") (name "+5V") (class "Default")
      (node (ref "C4") (pin "1") (pinfunction "1_1") (pintype "passive"))
      (node (ref "L1") (pin "1") (pinfunction "1_1") (pintype "passive"))
      (node (ref "R2") (pin "2") (pinfunction "2_2") (pintype "passive"))
    )
    (net (code "2") (name "+12V") (class "Default")
      (node (ref "C1") (pin "+") (pinfunction "+_+") (pintype "passive"))
      (node (ref "C1") (pin "-") (pinfunction "-_-") (pintype "passive"))
      (node (ref "C2") (pin "1") (pinfunction "1_1") (pintype "passive"))
      (node (ref "D2") (pin "C") (pinfunction "C_C") (pintype "passive"))
      (node (ref "D3") (pin "C") (pinfunction "C_C") (pintype "passive"))
      (node (ref "D6") (pin "C") (pinfunction "C_C") (pintype "passive"))
      (node (ref "D7") (pin "C") (pinfunction "C_C") (pintype "passive"))
      (node (ref "JP12") (pin "2") (pinfunction "2_2") (pintype "passive"))
      (node (ref "K1") (pin "1") (pinfunction "1_1") (pintype "passive"))
      (node (ref "K2") (pin "1") (pinfunction "1_1") (pintype "passive"))
      (node (ref "K3") (pin "1") (pinfunction "1_1") (pintype "passive"))
      (node (ref "K4") (pin "1") (pinfunction "1_1") (pintype "passive"))
      (node (ref "L3") (pin "2") (pinfunction "2_2") (pintype "passive"))
      (node (ref "R8") (pin "2") (pinfunction "2_2") (pintype "passive"))
      (node (ref "U$18") (pin "3") (pinfunction "VIN_3") (pintype "bidirectional"))
      (node (ref "U$18") (pin "5") (pinfunction "EN_5") (pintype "bidirectional"))
    )
    (net (code "3") (name "3.3V") (class "Default")
      (node (ref "C16") (pin "A") (pinfunction "+_A") (pintype "passive"))
      (node (ref "C23") (pin "1") (pinfunction "1_1") (pintype "passive"))
      (node (ref "C27") (pin "1") (pinfunction "1_1") (pintype "passive"))
      (node (ref "C28") (pin "1") (pinfunction "1_1") (pintype "passive"))
      (node (ref "C33") (pin "1") (pinfunction "1_1") (pintype "passive"))
      (node (ref "C34") (pin "1") (pinfunction "1_1") (pintype "passive"))
      (node (ref "C35") (pin "1") (pinfunction "1_1") (pintype "passive"))
      (node (ref "C38") (pin "1") (pinfunction "1_1") (pintype "passive"))
      (node (ref "C39") (pin "1") (pinfunction "1_1") (pintype "passive"))
      (node (ref "C45") (pin "1") (pinfunction "1_1") (pintype "passive"))
      (node (ref "C46") (pin "1") (pinfunction "1_1") (pintype "passive"))
      (node (ref "C47") (pin "1") (pinfunction "1_1") (pintype "passive"))
      (node (ref "C48") (pin "1") (pinfunction "1_1") (pintype "passive"))
      (node (ref "C49") (pin "1") (pinfunction "1_1") (pintype "passive"))
      (node (ref "C5") (pin "A") (pinfunction "+_A") (pintype "passive"))
      (node (ref "C50") (pin "1") (pinfunction "1_1") (pintype "passive"))
      (node (ref "C6") (pin "1") (pinfunction "1_1") (pintype "passive"))
      (node (ref "C7") (pin "1") (pinfunction "1_1") (pintype "passive"))
      (node (ref "C8") (pin "1") (pinfunction "1_1") (pintype "passive"))
      (node (ref "C9") (pin "1") (pinfunction "1_1") (pintype "passive"))
      (node (ref "D5") (pin "1") (pinfunction "A1_1") (pintype "passive"))
      (node (ref "IC5") (pin "5") (pinfunction "VDD_5") (pintype "power_in"))
      (node (ref "JP11") (pin "4") (pinfunction "4_4") (pintype "passive"))
      (node (ref "JP12") (pin "1") (pinfunction "1_1") (pintype "passive"))
      (node (ref "JP2") (pin "4") (pinfunction "4_4") (pintype "passive"))
      (node (ref "L4") (pin "2") (pinfunction "2_2") (pintype "passive"))
      (node (ref "L5") (pin "2") (pinfunction "2_2") (pintype "passive"))
      (node (ref "R11") (pin "2") (pinfunction "2_2") (pintype "passive"))
      (node (ref "R20") (pin "2") (pinfunction "2_2") (pintype "passive"))
      (node (ref "R28") (pin "1") (pinfunction "1_1") (pintype "passive"))
      (node (ref "R29") (pin "1") (pinfunction "1_1") (pintype "passive"))
      (node (ref "R30") (pin "1") (pinfunction "CCW_1") (pintype "passive"))
      (node (ref "R4") (pin "2") (pinfunction "2_2") (pintype "passive"))
      (node (ref "R43") (pin "2") (pinfunction "2_2") (pintype "passive"))
      (node (ref "R44") (pin "1") (pinfunction "1_1") (pintype "passive"))
      (node (ref "R45") (pin "2") (pinfunction "2_2") (pintype "passive"))
      (node (ref "U$1") (pin "12") (pinfunction "VDDPLL_12") (pintype "bidirectional"))
      (node (ref "U$1") (pin "15") (pinfunction "VDDRX_15") (pintype "bidirectional"))
      (node (ref "U$1") (pin "18") (pinfunction "VDDTX_18") (pintype "bidirectional"))
      (node (ref "U$1") (pin "4") (pinfunction "VDDOSC_4") (pintype "bidirectional"))
      (node (ref "U$1") (pin "44") (pinfunction "VDD_44") (pintype "bidirectional"))
      (node (ref "U$10") (pin "P$2") (pinfunction "P$2_P$2") (pintype "bidirectional"))
      (node (ref "U$11") (pin "P$2") (pinfunction "P$2_P$2") (pintype "bidirectional"))
      (node (ref "U$12") (pin "P$2") (pinfunction "P$2_P$2") (pintype "bidirectional"))
      (node (ref "U$13") (pin "P$2") (pinfunction "P$2_P$2") (pintype "bidirectional"))
      (node (ref "U$3") (pin "12") (pinfunction "VDDPLL_12") (pintype "bidirectional"))
      (node (ref "U$3") (pin "15") (pinfunction "VDDRX_15") (pintype "bidirectional"))
      (node (ref "U$3") (pin "18") (pinfunction "VDDTX_18") (pintype "bidirectional"))
      (node (ref "U$3") (pin "4") (pinfunction "VDDOSC_4") (pintype "bidirectional"))
      (node (ref "U$3") (pin "44") (pinfunction "VDD_44") (pintype "bidirectional"))
      (node (ref "U$4") (pin "P$3") (pinfunction "VCC_P$3") (pintype "bidirectional"))
      (node (ref "U$5") (pin "1") (pinfunction "VDD_1") (pintype "bidirectional"))
      (node (ref "U$5") (pin "17") (pinfunction "VDD_17") (pintype "bidirectional"))
      (node (ref "U$5") (pin "5") (pinfunction "VDDA_5") (pintype "bidirectional"))
      (node (ref "U$6") (pin "P$2") (pinfunction "P$2_P$2") (pintype "bidirectional"))
      (node (ref "U$7") (pin "P$2") (pinfunction "P$2_P$2") (pintype "bidirectional"))
      (node (ref "U$8") (pin "P$2") (pinfunction "P$2_P$2") (pintype "bidirectional"))
      (node (ref "U$9") (pin "P$2") (pinfunction "P$2_P$2") (pintype "bidirectional"))
      (node (ref "U2") (pin "24") (pinfunction "VDD_1_24") (pintype "bidirectional"))
      (node (ref "U2") (pin "36") (pinfunction "VDD_2_36") (pintype "power_in"))
      (node (ref "U2") (pin "48") (pinfunction "VDD_3_48") (pintype "power_in"))
      (node (ref "U2") (pin "9") (pinfunction "VDDA_9") (pintype "power_in"))
      (node (ref "U5") (pin "8") (pinfunction "VCC_8") (pintype "power_in"))
      (node (ref "U6") (pin "15") (pinfunction "A_15") (pintype "power_in"))
      (node (ref "U6") (pin "2") (pinfunction "VDD_2") (pintype "power_in"))
    )
    (net (code "4") (name "232_RX") (class "Default")
      (node (ref "U4") (pin "13") (pinfunction "R1IN_13") (pintype "input"))
      (node (ref "X1") (pin "3") (pinfunction "3_3") (pintype "passive"))
    )
    (net (code "5") (name "232_TX") (class "Default")
      (node (ref "U4") (pin "14") (pinfunction "T1OUT_14") (pintype "output"))
      (node (ref "X1") (pin "2") (pinfunction "2_2") (pintype "passive"))
    )
    (net (code "6") (name "DAISY_MUX") (class "Default")
      (node (ref "JP12") (pin "5") (pinfunction "5_5") (pintype "passive"))
      (node (ref "U$4") (pin "P$5") (pinfunction "I0_P$5") (pintype "bidirectional"))
    )
    (net (code "7") (name "DAISY_RX0") (class "Default")
      (node (ref "U$4") (pin "P$6") (pinfunction "Z_P$6") (pintype "bidirectional"))
      (node (ref "U2") (pin "13") (pinfunction "PA3_13") (pintype "bidirectional"))
    )
    (net (code "8") (name "DAISY_RX1") (class "Default")
      (node (ref "U$5") (pin "20") (pinfunction "PA10_20") (pintype "bidirectional"))
      (node (ref "U2") (pin "12") (pinfunction "PA2_12") (pintype "bidirectional"))
    )
    (net (code "9") (name "DAISY_RX2") (class "Default")
      (node (ref "JP12") (pin "3") (pinfunction "3_3") (pintype "passive"))
      (node (ref "U$4") (pin "P$1") (pinfunction "I1_P$1") (pintype "bidirectional"))
      (node (ref "U$5") (pin "19") (pinfunction "PA9_19") (pintype "bidirectional"))
    )
    (net (code "10") (name "DI_0") (class "Default")
      (node (ref "R32") (pin "1") (pinfunction "1_1") (pintype "passive"))
      (node (ref "U$5") (pin "6") (pinfunction "PA0_6") (pintype "bidirectional"))
      (node (ref "U$6") (pin "P$1") (pinfunction "P$1_P$1") (pintype "bidirectional"))
    )
    (net (code "11") (name "DI_1") (class "Default")
      (node (ref "R31") (pin "1") (pinfunction "1_1") (pintype "passive"))
      (node (ref "U$5") (pin "7") (pinfunction "PA1_7") (pintype "bidirectional"))
      (node (ref "U$7") (pin "P$1") (pinfunction "P$1_P$1") (pintype "bidirectional"))
    )
    (net (code "12") (name "DI_2") (class "Default")
      (node (ref "R33") (pin "1") (pinfunction "1_1") (pintype "passive"))
      (node (ref "U$13") (pin "P$1") (pinfunction "P$1_P$1") (pintype "bidirectional"))
      (node (ref "U$5") (pin "8") (pinfunction "PA2_8") (pintype "bidirectional"))
    )
    (net (code "13") (name "DI_3") (class "Default")
      (node (ref "R34") (pin "1") (pinfunction "1_1") (pintype "passive"))
      (node (ref "U$5") (pin "9") (pinfunction "PA3_9") (pintype "bidirectional"))
      (node (ref "U$8") (pin "P$1") (pinfunction "P$1_P$1") (pintype "bidirectional"))
    )
    (net (code "14") (name "DI_4") (class "Default")
      (node (ref "R35") (pin "1") (pinfunction "1_1") (pintype "passive"))
      (node (ref "U$12") (pin "P$1") (pinfunction "P$1_P$1") (pintype "bidirectional"))
      (node (ref "U$5") (pin "10") (pinfunction "PA4_10") (pintype "bidirectional"))
    )
    (net (code "15") (name "DI_5") (class "Default")
      (node (ref "R36") (pin "1") (pinfunction "1_1") (pintype "passive"))
      (node (ref "U$5") (pin "11") (pinfunction "PA5_11") (pintype "bidirectional"))
      (node (ref "U$9") (pin "P$1") (pinfunction "P$1_P$1") (pintype "bidirectional"))
    )
    (net (code "16") (name "DI_6") (class "Default")
      (node (ref "R37") (pin "1") (pinfunction "1_1") (pintype "passive"))
      (node (ref "U$11") (pin "P$1") (pinfunction "P$1_P$1") (pintype "bidirectional"))
      (node (ref "U$5") (pin "12") (pinfunction "PA6_12") (pintype "bidirectional"))
    )
    (net (code "17") (name "DI_7") (class "Default")
      (node (ref "R38") (pin "1") (pinfunction "1_1") (pintype "passive"))
      (node (ref "U$10") (pin "P$1") (pinfunction "P$1_P$1") (pintype "bidirectional"))
      (node (ref "U$5") (pin "13") (pinfunction "PA7_13") (pintype "bidirectional"))
    )
    (net (code "18") (name "DO_0") (class "Default")
      (node (ref "R42") (pin "1") (pinfunction "1_1") (pintype "passive"))
      (node (ref "T1") (pin "1") (pinfunction "G_1") (pintype "passive"))
      (node (ref "U$5") (pin "14") (pinfunction "PB0_14") (pintype "bidirectional"))
    )
    (net (code "19") (name "DO_1") (class "Default")
      (node (ref "R41") (pin "1") (pinfunction "1_1") (pintype "passive"))
      (node (ref "T2") (pin "1") (pinfunction "G_1") (pintype "passive"))
      (node (ref "U$5") (pin "15") (pinfunction "PB1_15") (pintype "bidirectional"))
    )
    (net (code "20") (name "DO_2") (class "Default")
      (node (ref "R40") (pin "1") (pinfunction "1_1") (pintype "passive"))
      (node (ref "T3") (pin "1") (pinfunction "G_1") (pintype "passive"))
      (node (ref "U$5") (pin "18") (pinfunction "PA8_18") (pintype "bidirectional"))
    )
    (net (code "21") (name "DO_3") (class "Default")
      (node (ref "R39") (pin "1") (pinfunction "1_1") (pintype "passive"))
      (node (ref "T4") (pin "1") (pinfunction "G_1") (pintype "passive"))
      (node (ref "U$5") (pin "21") (pinfunction "PA11_21") (pintype "bidirectional"))
    )
    (net (code "22") (name "GND") (class "Default")
      (node (ref "BAT1") (pin "2") (pinfunction "-_2") (pintype "power_in"))
      (node (ref "C10") (pin "2") (pinfunction "2_2") (pintype "passive"))
      (node (ref "C11") (pin "2") (pinfunction "2_2") (pintype "passive"))
      (node (ref "C12") (pin "2") (pinfunction "2_2") (pintype "passive"))
      (node (ref "C13") (pin "2") (pinfunction "2_2") (pintype "passive"))
      (node (ref "C14") (pin "2") (pinfunction "2_2") (pintype "passive"))
      (node (ref "C15") (pin "-") (pinfunction "-_-") (pintype "passive"))
      (node (ref "C16") (pin "C") (pinfunction "-_C") (pintype "passive"))
      (node (ref "C17") (pin "2") (pinfunction "2_2") (pintype "passive"))
      (node (ref "C2") (pin "2") (pinfunction "2_2") (pintype "passive"))
      (node (ref "C20") (pin "1") (pinfunction "1_1") (pintype "passive"))
      (node (ref "C21") (pin "1") (pinfunction "1_1") (pintype "passive"))
      (node (ref "C22") (pin "1") (pinfunction "1_1") (pintype "passive"))
      (node (ref "C23") (pin "2") (pinfunction "2_2") (pintype "passive"))
      (node (ref "C24") (pin "2") (pinfunction "2_2") (pintype "passive"))
      (node (ref "C25") (pin "2") (pinfunction "2_2") (pintype "passive"))
      (node (ref "C26") (pin "C") (pinfunction "-_C") (pintype "passive"))
      (node (ref "C27") (pin "2") (pinfunction "2_2") (pintype "passive"))
      (node (ref "C28") (pin "2") (pinfunction "2_2") (pintype "passive"))
      (node (ref "C29") (pin "2") (pinfunction "2_2") (pintype "passive"))
      (node (ref "C32") (pin "1") (pinfunction "1_1") (pintype "passive"))
      (node (ref "C33") (pin "2") (pinfunction "2_2") (pintype "passive"))
      (node (ref "C34") (pin "2") (pinfunction "2_2") (pintype "passive"))
      (node (ref "C35") (pin "2") (pinfunction "2_2") (pintype "passive"))
      (node (ref "C36") (pin "2") (pinfunction "2_2") (pintype "passive"))
      (node (ref "C37") (pin "2") (pinfunction "2_2") (pintype "passive"))
      (node (ref "C38") (pin "2") (pinfunction "2_2") (pintype "passive"))
      (node (ref "C39") (pin "2") (pinfunction "2_2") (pintype "passive"))
      (node (ref "C4") (pin "2") (pinfunction "2_2") (pintype "passive"))
      (node (ref "C40") (pin "C") (pinfunction "-_C") (pintype "passive"))
      (node (ref "C41") (pin "2") (pinfunction "2_2") (pintype "passive"))
      (node (ref "C44") (pin "1") (pinfunction "1_1") (pintype "passive"))
      (node (ref "C45") (pin "2") (pinfunction "2_2") (pintype "passive"))
      (node (ref "C46") (pin "2") (pinfunction "2_2") (pintype "passive"))
      (node (ref "C47") (pin "2") (pinfunction "2_2") (pintype "passive"))
      (node (ref "C48") (pin "2") (pinfunction "2_2") (pintype "passive"))
      (node (ref "C49") (pin "2") (pinfunction "2_2") (pintype "passive"))
      (node (ref "C5") (pin "C") (pinfunction "-_C") (pintype "passive"))
      (node (ref "C50") (pin "2") (pinfunction "2_2") (pintype "passive"))
      (node (ref "C6") (pin "2") (pinfunction "2_2") (pintype "passive"))
      (node (ref "C7") (pin "2") (pinfunction "2_2") (pintype "passive"))
      (node (ref "C8") (pin "2") (pinfunction "2_2") (pintype "passive"))
      (node (ref "C9") (pin "2") (pinfunction "2_2") (pintype "passive"))
      (node (ref "D4") (pin "A") (pinfunction "A_A") (pintype "passive"))
      (node (ref "IC5") (pin "2") (pinfunction "GND_2") (pintype "power_in"))
      (node (ref "J2") (pin "10") (pinfunction "G-_10") (pintype "bidirectional"))
      (node (ref "J2") (pin "12") (pinfunction "Y-_12") (pintype "bidirectional"))
      (node (ref "J2") (pin "8") (pinfunction "GND_8") (pintype "bidirectional"))
      (node (ref "J2") (pin "SHIELD0") (pinfunction "SHIELD0_SHIELD0") (pintype "bidirectional"))
      (node (ref "J2") (pin "SHIELD1") (pinfunction "SHIELD1_SHIELD1") (pintype "bidirectional"))
      (node (ref "J3") (pin "10") (pinfunction "G-_10") (pintype "bidirectional"))
      (node (ref "J3") (pin "12") (pinfunction "Y-_12") (pintype "bidirectional"))
      (node (ref "J3") (pin "8") (pinfunction "GND_8") (pintype "bidirectional"))
      (node (ref "J3") (pin "SHIELD0") (pinfunction "SHIELD0_SHIELD0") (pintype "bidirectional"))
      (node (ref "J3") (pin "SHIELD1") (pinfunction "SHIELD1_SHIELD1") (pintype "bidirectional"))
      (node (ref "JP11") (pin "1") (pinfunction "1_1") (pintype "passive"))
      (node (ref "JP12") (pin "7") (pinfunction "7_7") (pintype "passive"))
      (node (ref "JP2") (pin "1") (pinfunction "1_1") (pintype "passive"))
      (node (ref "JP3") (pin "GND") (pinfunction "GND_GND") (pintype "bidirectional"))
      (node (ref "JP4") (pin "1") (pinfunction "1_1") (pintype "passive"))
      (node (ref "JP5") (pin "1") (pinfunction "1_1") (pintype "passive"))
      (node (ref "JP5") (pin "2") (pinfunction "2_2") (pintype "passive"))
      (node (ref "JP7") (pin "1") (pinfunction "1_1") (pintype "passive"))
      (node (ref "LED1") (pin "C") (pinfunction "C_C") (pintype "passive"))
      (node (ref "LED10") (pin "C") (pinfunction "C_C") (pintype "passive"))
      (node (ref "LED11") (pin "C") (pinfunction "C_C") (pintype "passive"))
      (node (ref "LED12") (pin "C") (pinfunction "C_C") (pintype "passive"))
      (node (ref "LED13") (pin "C") (pinfunction "C_C") (pintype "passive"))
      (node (ref "LED2") (pin "C") (pinfunction "C_C") (pintype "passive"))
      (node (ref "LED3") (pin "C") (pinfunction "C_C") (pintype "passive"))
      (node (ref "LED4") (pin "C") (pinfunction "C_C") (pintype "passive"))
      (node (ref "LED5") (pin "C") (pinfunction "C_C") (pintype "passive"))
      (node (ref "LED6") (pin "C") (pinfunction "C_C") (pintype "passive"))
      (node (ref "LED7") (pin "C") (pinfunction "C_C") (pintype "passive"))
      (node (ref "LED8") (pin "C") (pinfunction "C_C") (pintype "passive"))
      (node (ref "LED9") (pin "C") (pinfunction "C_C") (pintype "passive"))
      (node (ref "R1") (pin "2") (pinfunction "2_2") (pintype "passive"))
      (node (ref "R10") (pin "1") (pinfunction "1_1") (pintype "passive"))
      (node (ref "R19") (pin "1") (pinfunction "1_1") (pintype "passive"))
      (node (ref "R3") (pin "1") (pinfunction "1_1") (pintype "passive"))
      (node (ref "R30") (pin "3") (pinfunction "CW_3") (pintype "passive"))
      (node (ref "R47") (pin "1") (pinfunction "1_1") (pintype "passive"))
      (node (ref "R48") (pin "2") (pinfunction "2_2") (pintype "passive"))
      (node (ref "R9") (pin "2") (pinfunction "2_2") (pintype "passive"))
      (node (ref "S1") (pin "3") (pinfunction "3_3") (pintype "passive"))
      (node (ref "S1") (pin "4") (pinfunction "4_4") (pintype "passive"))
      (node (ref "S2") (pin "3") (pinfunction "3_3") (pintype "passive"))
      (node (ref "S2") (pin "4") (pinfunction "4_4") (pintype "passive"))
      (node (ref "S3") (pin "3") (pinfunction "3_3") (pintype "passive"))
      (node (ref "S3") (pin "4") (pinfunction "4_4") (pintype "passive"))
      (node (ref "S4") (pin "3") (pinfunction "3_3") (pintype "passive"))
      (node (ref "S4") (pin "4") (pinfunction "4_4") (pintype "passive"))
      (node (ref "S5") (pin "3") (pinfunction "3_3") (pintype "passive"))
      (node (ref "S5") (pin "4") (pinfunction "4_4") (pintype "passive"))
      (node (ref "T1") (pin "2") (pinfunction "S_2") (pintype "passive"))
      (node (ref "T2") (pin "2") (pinfunction "S_2") (pintype "passive"))
      (node (ref "T3") (pin "2") (pinfunction "S_2") (pintype "passive"))
      (node (ref "T4") (pin "2") (pinfunction "S_2") (pintype "passive"))
      (node (ref "U$1") (pin "1") (pinfunction "VSSOSC_1") (pintype "bidirectional"))
      (node (ref "U$1") (pin "13") (pinfunction "VSSPLL_13") (pintype "bidirectional"))
      (node (ref "U$1") (pin "14") (pinfunction "VSSRX_14") (pintype "bidirectional"))
      (node (ref "U$1") (pin "19") (pinfunction "VSSTX1_19") (pintype "bidirectional"))
      (node (ref "U$1") (pin "22") (pinfunction "VSSTX2_22") (pintype "bidirectional"))
      (node (ref "U$1") (pin "33") (pinfunction "VSS1_33") (pintype "bidirectional"))
      (node (ref "U$1") (pin "42") (pinfunction "VSS2_42") (pintype "bidirectional"))
      (node (ref "U$18") (pin "1") (pinfunction "GND_1") (pintype "bidirectional"))
      (node (ref "U$2") (pin "P$2") (pinfunction "P$2_P$2") (pintype "bidirectional"))
      (node (ref "U$3") (pin "1") (pinfunction "VSSOSC_1") (pintype "bidirectional"))
      (node (ref "U$3") (pin "13") (pinfunction "VSSPLL_13") (pintype "bidirectional"))
      (node (ref "U$3") (pin "14") (pinfunction "VSSRX_14") (pintype "bidirectional"))
      (node (ref "U$3") (pin "19") (pinfunction "VSSTX1_19") (pintype "bidirectional"))
      (node (ref "U$3") (pin "22") (pinfunction "VSSTX2_22") (pintype "bidirectional"))
      (node (ref "U$3") (pin "33") (pinfunction "VSS1_33") (pintype "bidirectional"))
      (node (ref "U$3") (pin "42") (pinfunction "VSS2_42") (pintype "bidirectional"))
      (node (ref "U$4") (pin "P$4") (pinfunction "GND_P$4") (pintype "bidirectional"))
      (node (ref "U$5") (pin "16") (pinfunction "VSS_16") (pintype "bidirectional"))
      (node (ref "U$5") (pin "32") (pinfunction "VSS_32") (pintype "bidirectional"))
      (node (ref "U2") (pin "23") (pinfunction "VSS_1_23") (pintype "bidirectional"))
      (node (ref "U2") (pin "35") (pinfunction "VSS_2_35") (pintype "passive"))
      (node (ref "U2") (pin "47") (pinfunction "VSS_3_47") (pintype "passive"))
      (node (ref "U2") (pin "8") (pinfunction "VSSA_8") (pintype "passive"))
      (node (ref "U3") (pin "4") (pinfunction "GND_4") (pintype "bidirectional"))
      (node (ref "U4") (pin "15") (pinfunction "GND_15") (pintype "passive"))
      (node (ref "U5") (pin "4") (pinfunction "GND_4") (pintype "passive"))
      (node (ref "U6") (pin "1") (pinfunction "VSS_1") (pintype "power_in"))
      (node (ref "U6") (pin "10") (pinfunction "DB3_10") (pintype "bidirectional"))
      (node (ref "U6") (pin "16") (pinfunction "K_16") (pintype "power_in"))
      (node (ref "U6") (pin "5") (pinfunction "R/W_5") (pintype "input"))
      (node (ref "U6") (pin "7") (pinfunction "DB0_7") (pintype "bidirectional"))
      (node (ref "U6") (pin "8") (pinfunction "DB1_8") (pintype "bidirectional"))
      (node (ref "U6") (pin "9") (pinfunction "DB2_9") (pintype "bidirectional"))
      (node (ref "X1") (pin "5") (pinfunction "5_5") (pintype "passive"))
    )
    (net (code "23") (name "G_RESET") (class "Default")
      (node (ref "C10") (pin "1") (pinfunction "1_1") (pintype "passive"))
      (node (ref "R4") (pin "1") (pinfunction "1_1") (pintype "passive"))
      (node (ref "S5") (pin "1") (pinfunction "1_1") (pintype "passive"))
      (node (ref "S5") (pin "2") (pinfunction "2_2") (pintype "passive"))
      (node (ref "U$5") (pin "4") (pinfunction "NRST_4") (pintype "bidirectional"))
      (node (ref "U2") (pin "7") (pinfunction "NRST_7") (pintype "bidirectional"))
    )
    (net (code "24") (name "I2C1_SCL") (class "Default")
      (node (ref "IC5") (pin "6") (pinfunction "SCL_6") (pintype "input"))
      (node (ref "JP4") (pin "2") (pinfunction "2_2") (pintype "passive"))
      (node (ref "R29") (pin "2") (pinfunction "2_2") (pintype "passive"))
      (node (ref "U2") (pin "42") (pinfunction "PB6_42") (pintype "bidirectional"))
    )
    (net (code "25") (name "I2C1_SDA") (class "Default")
      (node (ref "IC5") (pin "1") (pinfunction "SDA_1") (pintype "bidirectional"))
      (node (ref "JP4") (pin "3") (pinfunction "3_3") (pintype "passive"))
      (node (ref "R28") (pin "2") (pinfunction "2_2") (pintype "passive"))
      (node (ref "U2") (pin "43") (pinfunction "PB7_43") (pintype "bidirectional"))
    )
    (net (code "26") (name "LA1") (class "Default")
      (node (ref "J2") (pin "9") (pinfunction "G+_9") (pintype "bidirectional"))
      (node (ref "R17") (pin "1") (pinfunction "1_1") (pintype "passive"))
    )
    (net (code "27") (name "LA2") (class "Default")
      (node (ref "J3") (pin "9") (pinfunction "G+_9") (pintype "bidirectional"))
      (node (ref "R26") (pin "1") (pinfunction "1_1") (pintype "passive"))
    )
    (net (code "28") (name "LB1") (class "Default")
      (node (ref "J2") (pin "11") (pinfunction "Y+_11") (pintype "bidirectional"))
      (node (ref "R18") (pin "1") (pinfunction "1_1") (pintype "passive"))
    )
    (net (code "29") (name "LB2") (class "Default")
      (node (ref "J3") (pin "11") (pinfunction "Y+_11") (pintype "bidirectional"))
      (node (ref "R27") (pin "1") (pinfunction "1_1") (pintype "passive"))
    )
    (net (code "30") (name "LCD_D4") (class "Default")
      (node (ref "U$5") (pin "27") (pinfunction "PB4_27") (pintype "bidirectional"))
      (node (ref "U6") (pin "11") (pinfunction "DB4_11") (pintype "bidirectional"))
    )
    (net (code "31") (name "LCD_D5") (class "Default")
      (node (ref "U$5") (pin "28") (pinfunction "PB5_28") (pintype "bidirectional"))
      (node (ref "U6") (pin "12") (pinfunction "DB5_12") (pintype "bidirectional"))
    )
    (net (code "32") (name "LCD_D6") (class "Default")
      (node (ref "U$5") (pin "29") (pinfunction "PB6_29") (pintype "bidirectional"))
      (node (ref "U6") (pin "13") (pinfunction "DB6_13") (pintype "bidirectional"))
    )
    (net (code "33") (name "LCD_D7") (class "Default")
      (node (ref "U$5") (pin "30") (pinfunction "PB7_30") (pintype "bidirectional"))
      (node (ref "U6") (pin "14") (pinfunction "DB7_14") (pintype "bidirectional"))
    )
    (net (code "34") (name "LCD_E") (class "Default")
      (node (ref "U$5") (pin "26") (pinfunction "PB3_26") (pintype "bidirectional"))
      (node (ref "U6") (pin "6") (pinfunction "E_6") (pintype "input"))
    )
    (net (code "35") (name "LCD_RS") (class "Default")
      (node (ref "U$5") (pin "25") (pinfunction "PA15_25") (pintype "bidirectional"))
      (node (ref "U6") (pin "4") (pinfunction "RS_4") (pintype "input"))
    )
    (net (code "36") (name "Net-(BAT1-+)") (class "Default")
      (node (ref "BAT1") (pin "1") (pinfunction "+_1") (pintype "power_in"))
      (node (ref "D5") (pin "2") (pinfunction "A2_2") (pintype "passive"))
    )
    (net (code "37") (name "Net-(C26-+)") (class "Default")
      (node (ref "C26") (pin "A") (pinfunction "+_A") (pintype "passive"))
      (node (ref "U$1") (pin "43") (pinfunction "VCAP_43") (pintype "bidirectional"))
    )
    (net (code "38") (name "Net-(C40-+)") (class "Default")
      (node (ref "C40") (pin "A") (pinfunction "+_A") (pintype "passive"))
      (node (ref "U$3") (pin "43") (pinfunction "VCAP_43") (pintype "bidirectional"))
    )
    (net (code "39") (name "Net-(D8-PadA)") (class "Default")
      (node (ref "D8") (pin "A") (pinfunction "A_A") (pintype "passive"))
      (node (ref "F1") (pin "2") (pinfunction "2_2") (pintype "bidirectional"))
      (node (ref "R1") (pin "1") (pinfunction "1_1") (pintype "passive"))
    )
    (net (code "40") (name "Net-(F1-Pad1)") (class "Default")
      (node (ref "F1") (pin "1") (pinfunction "1_1") (pintype "bidirectional"))
      (node (ref "U$2") (pin "P$1") (pinfunction "P$1_P$1") (pintype "bidirectional"))
    )
    (net (code "41") (name "Net-(JP3-PadD+)") (class "Default")
      (node (ref "JP3") (pin "D+") (pinfunction "D+_D+") (pintype "bidirectional"))
      (node (ref "R6") (pin "2") (pinfunction "2_2") (pintype "passive"))
    )
    (net (code "42") (name "Net-(JP3-PadD-)") (class "Default")
      (node (ref "JP3") (pin "D-") (pinfunction "D-_D-") (pintype "bidirectional"))
      (node (ref "R5") (pin "2") (pinfunction "2_2") (pintype "passive"))
    )
    (net (code "43") (name "Net-(K1-PadO)") (class "Default")
      (node (ref "K1") (pin "O") (pinfunction "O_O") (pintype "passive"))
      (node (ref "U$14") (pin "P$1") (pinfunction "P$1_P$1") (pintype "bidirectional"))
    )
    (net (code "44") (name "Net-(K1-PadP)") (class "Default")
      (node (ref "K1") (pin "P") (pinfunction "P_P") (pintype "passive"))
      (node (ref "U$14") (pin "P$2") (pinfunction "P$2_P$2") (pintype "bidirectional"))
    )
    (net (code "45") (name "Net-(K1-PadS)") (class "Default")
      (node (ref "K1") (pin "S") (pinfunction "S_S") (pintype "passive"))
      (node (ref "U$14") (pin "P$3") (pinfunction "P$3_P$3") (pintype "bidirectional"))
    )
    (net (code "46") (name "Net-(K2-PadO)") (class "Default")
      (node (ref "K2") (pin "O") (pinfunction "O_O") (pintype "passive"))
      (node (ref "U$15") (pin "P$1") (pinfunction "P$1_P$1") (pintype "bidirectional"))
    )
    (net (code "47") (name "Net-(K2-PadP)") (class "Default")
      (node (ref "K2") (pin "P") (pinfunction "P_P") (pintype "passive"))
      (node (ref "U$15") (pin "P$2") (pinfunction "P$2_P$2") (pintype "bidirectional"))
    )
    (net (code "48") (name "Net-(K2-PadS)") (class "Default")
      (node (ref "K2") (pin "S") (pinfunction "S_S") (pintype "passive"))
      (node (ref "U$15") (pin "P$3") (pinfunction "P$3_P$3") (pintype "bidirectional"))
    )
    (net (code "49") (name "Net-(K3-PadO)") (class "Default")
      (node (ref "K3") (pin "O") (pinfunction "O_O") (pintype "passive"))
      (node (ref "U$16") (pin "P$1") (pinfunction "P$1_P$1") (pintype "bidirectional"))
    )
    (net (code "50") (name "Net-(K3-PadP)") (class "Default")
      (node (ref "K3") (pin "P") (pinfunction "P_P") (pintype "passive"))
      (node (ref "U$16") (pin "P$2") (pinfunction "P$2_P$2") (pintype "bidirectional"))
    )
    (net (code "51") (name "Net-(K3-PadS)") (class "Default")
      (node (ref "K3") (pin "S") (pinfunction "S_S") (pintype "passive"))
      (node (ref "U$16") (pin "P$3") (pinfunction "P$3_P$3") (pintype "bidirectional"))
    )
    (net (code "52") (name "Net-(K4-PadO)") (class "Default")
      (node (ref "K4") (pin "O") (pinfunction "O_O") (pintype "passive"))
      (node (ref "U$17") (pin "P$1") (pinfunction "P$1_P$1") (pintype "bidirectional"))
    )
    (net (code "53") (name "Net-(K4-PadP)") (class "Default")
      (node (ref "K4") (pin "P") (pinfunction "P_P") (pintype "passive"))
      (node (ref "U$17") (pin "P$2") (pinfunction "P$2_P$2") (pintype "bidirectional"))
    )
    (net (code "54") (name "Net-(K4-PadS)") (class "Default")
      (node (ref "K4") (pin "S") (pinfunction "S_S") (pintype "passive"))
      (node (ref "U$17") (pin "P$3") (pinfunction "P$3_P$3") (pintype "bidirectional"))
    )
    (net (code "55") (name "Net-(L4-Pad1)") (class "Default")
      (node (ref "L4") (pin "1") (pinfunction "1_1") (pintype "passive"))
      (node (ref "R12") (pin "2") (pinfunction "2_2") (pintype "passive"))
      (node (ref "R13") (pin "2") (pinfunction "2_2") (pintype "passive"))
      (node (ref "R16") (pin "2") (pinfunction "2_2") (pintype "passive"))
    )
    (net (code "56") (name "Net-(L5-Pad1)") (class "Default")
      (node (ref "L5") (pin "1") (pinfunction "1_1") (pintype "passive"))
      (node (ref "R21") (pin "2") (pinfunction "2_2") (pintype "passive"))
      (node (ref "R22") (pin "2") (pinfunction "2_2") (pintype "passive"))
      (node (ref "R25") (pin "2") (pinfunction "2_2") (pintype "passive"))
    )
    (net (code "57") (name "Net-(LED1-PadA)") (class "Default")
      (node (ref "LED1") (pin "A") (pinfunction "A_A") (pintype "passive"))
      (node (ref "R31") (pin "2") (pinfunction "2_2") (pintype "passive"))
    )
    (net (code "58") (name "Net-(LED2-PadA)") (class "Default")
      (node (ref "LED2") (pin "A") (pinfunction "A_A") (pintype "passive"))
      (node (ref "R33") (pin "2") (pinfunction "2_2") (pintype "passive"))
    )
    (net (code "59") (name "Net-(LED3-PadA)") (class "Default")
      (node (ref "LED3") (pin "A") (pinfunction "A_A") (pintype "passive"))
      (node (ref "R34") (pin "2") (pinfunction "2_2") (pintype "passive"))
    )
    (net (code "60") (name "Net-(LED4-PadA)") (class "Default")
      (node (ref "LED4") (pin "A") (pinfunction "A_A") (pintype "passive"))
      (node (ref "R35") (pin "2") (pinfunction "2_2") (pintype "passive"))
    )
    (net (code "61") (name "Net-(LED5-PadA)") (class "Default")
      (node (ref "LED5") (pin "A") (pinfunction "A_A") (pintype "passive"))
      (node (ref "R36") (pin "2") (pinfunction "2_2") (pintype "passive"))
    )
    (net (code "62") (name "Net-(LED6-PadA)") (class "Default")
      (node (ref "LED6") (pin "A") (pinfunction "A_A") (pintype "passive"))
      (node (ref "R38") (pin "2") (pinfunction "2_2") (pintype "passive"))
    )
    (net (code "63") (name "Net-(LED7-PadA)") (class "Default")
      (node (ref "LED7") (pin "A") (pinfunction "A_A") (pintype "passive"))
      (node (ref "R37") (pin "2") (pinfunction "2_2") (pintype "passive"))
    )
    (net (code "64") (name "Net-(LED8-PadA)") (class "Default")
      (node (ref "LED8") (pin "A") (pinfunction "A_A") (pintype "passive"))
      (node (ref "R32") (pin "2") (pinfunction "2_2") (pintype "passive"))
    )
    (net (code "65") (name "Net-(LED9-PadA)") (class "Default")
      (node (ref "LED9") (pin "A") (pinfunction "A_A") (pintype "passive"))
      (node (ref "R39") (pin "2") (pinfunction "2_2") (pintype "passive"))
    )
    (net (code "66") (name "Net-(LED10-PadA)") (class "Default")
      (node (ref "LED10") (pin "A") (pinfunction "A_A") (pintype "passive"))
      (node (ref "R40") (pin "2") (pinfunction "2_2") (pintype "passive"))
    )
    (net (code "67") (name "Net-(LED11-PadA)") (class "Default")
      (node (ref "LED11") (pin "A") (pinfunction "A_A") (pintype "passive"))
      (node (ref "R41") (pin "2") (pinfunction "2_2") (pintype "passive"))
    )
    (net (code "68") (name "Net-(LED12-PadA)") (class "Default")
      (node (ref "LED12") (pin "A") (pinfunction "A_A") (pintype "passive"))
      (node (ref "R42") (pin "2") (pinfunction "2_2") (pintype "passive"))
    )
    (net (code "69") (name "Net-(LED13-PadA)") (class "Default")
      (node (ref "LED13") (pin "A") (pinfunction "A_A") (pintype "passive"))
      (node (ref "R44") (pin "2") (pinfunction "2_2") (pintype "passive"))
    )
    (net (code "70") (name "Net-(R30-WIPER)") (class "Default")
      (node (ref "R30") (pin "2") (pinfunction "WIPER_2") (pintype "passive"))
      (node (ref "U6") (pin "3") (pinfunction "VO_3") (pintype "bidirectional"))
    )
    (net (code "71") (name "Net-(T1-D)") (class "Default")
      (node (ref "D7") (pin "A") (pinfunction "A_A") (pintype "passive"))
      (node (ref "K1") (pin "2") (pinfunction "2_2") (pintype "passive"))
      (node (ref "T1") (pin "3") (pinfunction "D_3") (pintype "passive"))
    )
    (net (code "72") (name "Net-(T2-D)") (class "Default")
      (node (ref "D6") (pin "A") (pinfunction "A_A") (pintype "passive"))
      (node (ref "K2") (pin "2") (pinfunction "2_2") (pintype "passive"))
      (node (ref "T2") (pin "3") (pinfunction "D_3") (pintype "passive"))
    )
    (net (code "73") (name "Net-(T3-D)") (class "Default")
      (node (ref "D2") (pin "A") (pinfunction "A_A") (pintype "passive"))
      (node (ref "K3") (pin "2") (pinfunction "2_2") (pintype "passive"))
      (node (ref "T3") (pin "3") (pinfunction "D_3") (pintype "passive"))
    )
    (net (code "74") (name "Net-(T4-D)") (class "Default")
      (node (ref "D3") (pin "A") (pinfunction "A_A") (pintype "passive"))
      (node (ref "K4") (pin "2") (pinfunction "2_2") (pintype "passive"))
      (node (ref "T4") (pin "3") (pinfunction "D_3") (pintype "passive"))
    )
    (net (code "75") (name "Net-(U$1-LEDA)") (class "Default")
      (node (ref "R17") (pin "2") (pinfunction "2_2") (pintype "passive"))
      (node (ref "U$1") (pin "10") (pinfunction "LEDA_10") (pintype "bidirectional"))
    )
    (net (code "76") (name "Net-(U$1-LEDB)") (class "Default")
      (node (ref "R18") (pin "2") (pinfunction "2_2") (pintype "passive"))
      (node (ref "U$1") (pin "9") (pinfunction "LEDB_9") (pintype "bidirectional"))
    )
    (net (code "77") (name "Net-(U$1-OSC1)") (class "Default")
      (node (ref "C24") (pin "1") (pinfunction "1_1") (pintype "passive"))
      (node (ref "U$1") (pin "3") (pinfunction "OSC1_3") (pintype "bidirectional"))
      (node (ref "Y3") (pin "P$1") (pinfunction "1_P$1") (pintype "passive"))
    )
    (net (code "78") (name "Net-(U$1-OSC2)") (class "Default")
      (node (ref "C25") (pin "1") (pinfunction "1_1") (pintype "passive"))
      (node (ref "U$1") (pin "2") (pinfunction "OSC2_2") (pintype "bidirectional"))
      (node (ref "Y3") (pin "P$2") (pinfunction "2_P$2") (pintype "passive"))
    )
    (net (code "79") (name "Net-(U$1-RBIAS)") (class "Default")
      (node (ref "R10") (pin "2") (pinfunction "2_2") (pintype "passive"))
      (node (ref "U$1") (pin "11") (pinfunction "RBIAS_11") (pintype "bidirectional"))
    )
    (net (code "80") (name "Net-(U$1-TPIN+)") (class "Default")
      (node (ref "C30") (pin "1") (pinfunction "1_1") (pintype "passive"))
      (node (ref "R15") (pin "2") (pinfunction "2_2") (pintype "passive"))
      (node (ref "U$1") (pin "16") (pinfunction "TPIN+_16") (pintype "bidirectional"))
    )
    (net (code "81") (name "Net-(U$1-TPIN-)") (class "Default")
      (node (ref "C31") (pin "1") (pinfunction "1_1") (pintype "passive"))
      (node (ref "R14") (pin "2") (pinfunction "2_2") (pintype "passive"))
      (node (ref "U$1") (pin "17") (pinfunction "TPIN-_17") (pintype "bidirectional"))
    )
    (net (code "82") (name "Net-(U$1-~{INT{slash}SPISEL})") (class "Default")
      (node (ref "R11") (pin "1") (pinfunction "1_1") (pintype "passive"))
      (node (ref "U$1") (pin "24") (pinfunction "~{INT/SPISEL}_24") (pintype "bidirectional"))
    )
    (net (code "83") (name "Net-(U$3-LEDA)") (class "Default")
      (node (ref "R26") (pin "2") (pinfunction "2_2") (pintype "passive"))
      (node (ref "U$3") (pin "10") (pinfunction "LEDA_10") (pintype "bidirectional"))
    )
    (net (code "84") (name "Net-(U$3-LEDB)") (class "Default")
      (node (ref "R27") (pin "2") (pinfunction "2_2") (pintype "passive"))
      (node (ref "U$3") (pin "9") (pinfunction "LEDB_9") (pintype "bidirectional"))
    )
    (net (code "85") (name "Net-(U$3-OSC1)") (class "Default")
      (node (ref "C36") (pin "1") (pinfunction "1_1") (pintype "passive"))
      (node (ref "U$3") (pin "3") (pinfunction "OSC1_3") (pintype "bidirectional"))
      (node (ref "Y4") (pin "P$1") (pinfunction "1_P$1") (pintype "passive"))
    )
    (net (code "86") (name "Net-(U$3-OSC2)") (class "Default")
      (node (ref "C37") (pin "1") (pinfunction "1_1") (pintype "passive"))
      (node (ref "U$3") (pin "2") (pinfunction "OSC2_2") (pintype "bidirectional"))
      (node (ref "Y4") (pin "P$2") (pinfunction "2_P$2") (pintype "passive"))
    )
    (net (code "87") (name "Net-(U$3-RBIAS)") (class "Default")
      (node (ref "R19") (pin "2") (pinfunction "2_2") (pintype "passive"))
      (node (ref "U$3") (pin "11") (pinfunction "RBIAS_11") (pintype "bidirectional"))
    )
    (net (code "88") (name "Net-(U$3-TPIN+)") (class "Default")
      (node (ref "C42") (pin "1") (pinfunction "1_1") (pintype "passive"))
      (node (ref "R24") (pin "2") (pinfunction "2_2") (pintype "passive"))
      (node (ref "U$3") (pin "16") (pinfunction "TPIN+_16") (pintype "bidirectional"))
    )
    (net (code "89") (name "Net-(U$3-TPIN-)") (class "Default")
      (node (ref "C43") (pin "1") (pinfunction "1_1") (pintype "passive"))
      (node (ref "R23") (pin "2") (pinfunction "2_2") (pintype "passive"))
      (node (ref "U$3") (pin "17") (pinfunction "TPIN-_17") (pintype "bidirectional"))
    )
    (net (code "90") (name "Net-(U$3-~{INT{slash}SPISEL})") (class "Default")
      (node (ref "R20") (pin "1") (pinfunction "1_1") (pintype "passive"))
      (node (ref "U$3") (pin "24") (pinfunction "~{INT/SPISEL}_24") (pintype "bidirectional"))
    )
    (net (code "91") (name "Net-(U$4-S)") (class "Default")
      (node (ref "JP12") (pin "8") (pinfunction "8_8") (pintype "passive"))
      (node (ref "R43") (pin "1") (pinfunction "1_1") (pintype "passive"))
      (node (ref "U$4") (pin "P$2") (pinfunction "S_P$2") (pintype "bidirectional"))
    )
    (net (code "92") (name "Net-(U$5-BOOT0)") (class "Default")
      (node (ref "R48") (pin "1") (pinfunction "1_1") (pintype "passive"))
      (node (ref "U$5") (pin "31") (pinfunction "BOOT0_31") (pintype "bidirectional"))
    )
    (net (code "93") (name "Net-(U$5-PA13{slash}SWDIO)") (class "Default")
      (node (ref "JP11") (pin "3") (pinfunction "3_3") (pintype "passive"))
      (node (ref "U$5") (pin "23") (pinfunction "PA13/SWDIO_23") (pintype "bidirectional"))
    )
    (net (code "94") (name "Net-(U$5-PA14{slash}SWCLK)") (class "Default")
      (node (ref "JP11") (pin "2") (pinfunction "2_2") (pintype "passive"))
      (node (ref "U$5") (pin "24") (pinfunction "PA14/SWCLK_24") (pintype "bidirectional"))
    )
    (net (code "95") (name "Net-(U$18-SW)") (class "Default")
      (node (ref "C3") (pin "1") (pinfunction "1_1") (pintype "passive"))
      (node (ref "L1") (pin "2") (pinfunction "2_2") (pintype "passive"))
      (node (ref "U$18") (pin "2") (pinfunction "SW_2") (pintype "bidirectional"))
    )
    (net (code "96") (name "Net-(U$18-VBST)") (class "Default")
      (node (ref "C3") (pin "2") (pinfunction "2_2") (pintype "passive"))
      (node (ref "U$18") (pin "6") (pinfunction "VBST_6") (pintype "bidirectional"))
    )
    (net (code "97") (name "Net-(U$18-VFB)") (class "Default")
      (node (ref "R2") (pin "1") (pinfunction "1_1") (pintype "passive"))
      (node (ref "R3") (pin "2") (pinfunction "2_2") (pintype "passive"))
      (node (ref "U$18") (pin "4") (pinfunction "VFB_4") (pintype "bidirectional"))
    )
    (net (code "98") (name "Net-(U2-BOOT0)") (class "Default")
      (node (ref "R47") (pin "2") (pinfunction "2_2") (pintype "passive"))
      (node (ref "U2") (pin "44") (pinfunction "BOOT0_44") (pintype "bidirectional"))
    )
    (net (code "99") (name "Net-(U2-PC14-OSC32_IN)") (class "Default")
      (node (ref "C12") (pin "1") (pinfunction "1_1") (pintype "passive"))
      (node (ref "U2") (pin "3") (pinfunction "PC14-OSC32_IN_3") (pintype "bidirectional"))
      (node (ref "Y1") (pin "1") (pinfunction "1_1") (pintype "passive"))
    )
    (net (code "100") (name "Net-(U2-PC15-OSC32_OUT)") (class "Default")
      (node (ref "C11") (pin "1") (pinfunction "1_1") (pintype "passive"))
      (node (ref "U2") (pin "4") (pinfunction "PC15-OSC32_OUT_4") (pintype "bidirectional"))
      (node (ref "Y1") (pin "4") (pinfunction "2_4") (pintype "passive"))
    )
    (net (code "101") (name "Net-(U2-PD0-OSC_IN)") (class "Default")
      (node (ref "C13") (pin "1") (pinfunction "1_1") (pintype "passive"))
      (node (ref "R46") (pin "2") (pinfunction "2_2") (pintype "passive"))
      (node (ref "U2") (pin "5") (pinfunction "PD0-OSC_IN_5") (pintype "bidirectional"))
      (node (ref "Y2") (pin "2") (pinfunction "2_2") (pintype "passive"))
    )
    (net (code "102") (name "Net-(U2-PD1-OSC_OUT)") (class "Default")
      (node (ref "C14") (pin "1") (pinfunction "1_1") (pintype "passive"))
      (node (ref "R46") (pin "1") (pinfunction "1_1") (pintype "passive"))
      (node (ref "U2") (pin "6") (pinfunction "PD1-OSC_OUT_6") (pintype "bidirectional"))
      (node (ref "Y2") (pin "1") (pinfunction "1_1") (pintype "passive"))
    )
    (net (code "103") (name "Net-(U3-COMP)") (class "Default")
      (node (ref "R8") (pin "1") (pinfunction "1_1") (pintype "passive"))
      (node (ref "R9") (pin "1") (pinfunction "1_1") (pintype "passive"))
      (node (ref "U3") (pin "5") (pinfunction "COMP_5") (pintype "bidirectional"))
    )
    (net (code "104") (name "Net-(U3-SWE)") (class "Default")
      (node (ref "D4") (pin "C") (pinfunction "C_C") (pintype "passive"))
      (node (ref "L3") (pin "1") (pinfunction "1_1") (pintype "passive"))
      (node (ref "U3") (pin "2") (pinfunction "SWE_2") (pintype "bidirectional"))
    )
    (net (code "105") (name "Net-(U3-TC)") (class "Default")
      (node (ref "C17") (pin "1") (pinfunction "1_1") (pintype "passive"))
      (node (ref "U3") (pin "3") (pinfunction "TC_3") (pintype "bidirectional"))
    )
    (net (code "106") (name "Net-(U4-C1+)") (class "Default")
      (node (ref "C18") (pin "1") (pinfunction "1_1") (pintype "passive"))
      (node (ref "U4") (pin "1") (pinfunction "C1+_1") (pintype "input"))
    )
    (net (code "107") (name "Net-(U4-C1-)") (class "Default")
      (node (ref "C18") (pin "2") (pinfunction "2_2") (pintype "passive"))
      (node (ref "U4") (pin "3") (pinfunction "C1-_3") (pintype "input"))
    )
    (net (code "108") (name "Net-(U4-C2+)") (class "Default")
      (node (ref "C19") (pin "2") (pinfunction "2_2") (pintype "passive"))
      (node (ref "U4") (pin "4") (pinfunction "C2+_4") (pintype "input"))
    )
    (net (code "109") (name "Net-(U4-C2-)") (class "Default")
      (node (ref "C19") (pin "1") (pinfunction "1_1") (pintype "passive"))
      (node (ref "U4") (pin "5") (pinfunction "C2-_5") (pintype "input"))
    )
    (net (code "110") (name "Net-(U4-V+)") (class "Default")
      (node (ref "C21") (pin "2") (pinfunction "2_2") (pintype "passive"))
      (node (ref "U4") (pin "2") (pinfunction "V+_2") (pintype "input"))
    )
    (net (code "111") (name "Net-(U4-V-)") (class "Default")
      (node (ref "C20") (pin "2") (pinfunction "2_2") (pintype "passive"))
      (node (ref "U4") (pin "6") (pinfunction "V-_6") (pintype "input"))
    )
    (net (code "112") (name "Net-(U4-VCC)") (class "Default")
      (node (ref "C22") (pin "2") (pinfunction "2_2") (pintype "passive"))
      (node (ref "U4") (pin "16") (pinfunction "VCC_16") (pintype "power_in"))
    )
    (net (code "113") (name "RX1+") (class "Default")
      (node (ref "C30") (pin "2") (pinfunction "2_2") (pintype "passive"))
      (node (ref "J2") (pin "4") (pinfunction "RD+_4") (pintype "bidirectional"))
    )
    (net (code "114") (name "RX1-") (class "Default")
      (node (ref "C31") (pin "2") (pinfunction "2_2") (pintype "passive"))
      (node (ref "J2") (pin "6") (pinfunction "RD-_6") (pintype "bidirectional"))
    )
    (net (code "115") (name "RX1_CT") (class "Default")
      (node (ref "C32") (pin "2") (pinfunction "2_2") (pintype "passive"))
      (node (ref "J2") (pin "5") (pinfunction "RXCT_5") (pintype "bidirectional"))
      (node (ref "R14") (pin "1") (pinfunction "1_1") (pintype "passive"))
      (node (ref "R15") (pin "1") (pinfunction "1_1") (pintype "passive"))
    )
    (net (code "116") (name "RX2+") (class "Default")
      (node (ref "C42") (pin "2") (pinfunction "2_2") (pintype "passive"))
      (node (ref "J3") (pin "4") (pinfunction "RD+_4") (pintype "bidirectional"))
    )
    (net (code "117") (name "RX2-") (class "Default")
      (node (ref "C43") (pin "2") (pinfunction "2_2") (pintype "passive"))
      (node (ref "J3") (pin "6") (pinfunction "RD-_6") (pintype "bidirectional"))
    )
    (net (code "118") (name "RX2_CT") (class "Default")
      (node (ref "C44") (pin "2") (pinfunction "2_2") (pintype "passive"))
      (node (ref "J3") (pin "5") (pinfunction "RXCT_5") (pintype "bidirectional"))
      (node (ref "R23") (pin "1") (pinfunction "1_1") (pintype "passive"))
      (node (ref "R24") (pin "1") (pinfunction "1_1") (pintype "passive"))
    )
    (net (code "119") (name "SPI1_MISO") (class "Default")
      (node (ref "JP1") (pin "2") (pinfunction "2_2") (pintype "passive"))
      (node (ref "U$1") (pin "35") (pinfunction "SO/WR/EN_35") (pintype "bidirectional"))
      (node (ref "U2") (pin "16") (pinfunction "PA6_16") (pintype "bidirectional"))
    )
    (net (code "120") (name "SPI1_MOSI") (class "Default")
      (node (ref "JP1") (pin "3") (pinfunction "3_3") (pintype "passive"))
      (node (ref "U$1") (pin "36") (pinfunction "SI/RD/~{RW}_36") (pintype "bidirectional"))
      (node (ref "U2") (pin "17") (pinfunction "PA7_17") (pintype "bidirectional"))
    )
    (net (code "121") (name "SPI1_SCK") (class "Default")
      (node (ref "JP1") (pin "4") (pinfunction "4_4") (pintype "passive"))
      (node (ref "U$1") (pin "37") (pinfunction "SCK/AL_37") (pintype "bidirectional"))
      (node (ref "U2") (pin "15") (pinfunction "PA5_15") (pintype "bidirectional"))
    )
    (net (code "122") (name "SPI1_SS1_ETH1") (class "Default")
      (node (ref "JP1") (pin "1") (pinfunction "1_1") (pintype "passive"))
      (node (ref "U$1") (pin "34") (pinfunction "CS/~{CS}_34") (pintype "bidirectional"))
      (node (ref "U2") (pin "18") (pinfunction "PB0_18") (pintype "bidirectional"))
    )
    (net (code "123") (name "SPI2_MISO") (class "Default")
      (node (ref "JP5") (pin "6") (pinfunction "6_6") (pintype "passive"))
      (node (ref "U$3") (pin "35") (pinfunction "SO/WR/EN_35") (pintype "bidirectional"))
      (node (ref "U2") (pin "28") (pinfunction "PB15_28") (pintype "bidirectional"))
      (node (ref "U5") (pin "2") (pinfunction "SO_(IO1)_2") (pintype "output"))
    )
    (net (code "124") (name "SPI2_MOSI") (class "Default")
      (node (ref "JP5") (pin "5") (pinfunction "5_5") (pintype "passive"))
      (node (ref "U$3") (pin "36") (pinfunction "SI/RD/~{RW}_36") (pintype "bidirectional"))
      (node (ref "U2") (pin "27") (pinfunction "PB14_27") (pintype "bidirectional"))
      (node (ref "U5") (pin "5") (pinfunction "SI_(IO0)_5") (pintype "bidirectional"))
    )
    (net (code "125") (name "SPI2_SCK") (class "Default")
      (node (ref "JP5") (pin "7") (pinfunction "7_7") (pintype "passive"))
      (node (ref "U$3") (pin "37") (pinfunction "SCK/AL_37") (pintype "bidirectional"))
      (node (ref "U2") (pin "26") (pinfunction "PB13_26") (pintype "bidirectional"))
      (node (ref "U5") (pin "6") (pinfunction "CLK_6") (pintype "input"))
    )
    (net (code "126") (name "SPI2_SS1_ETH2") (class "Default")
      (node (ref "JP5") (pin "3") (pinfunction "3_3") (pintype "passive"))
      (node (ref "U$3") (pin "34") (pinfunction "CS/~{CS}_34") (pintype "bidirectional"))
      (node (ref "U2") (pin "29") (pinfunction "PA8_29") (pintype "bidirectional"))
    )
    (net (code "127") (name "SPI2_SS2_FLASH") (class "Default")
      (node (ref "JP5") (pin "4") (pinfunction "4_4") (pintype "passive"))
      (node (ref "U2") (pin "25") (pinfunction "PB12_25") (pintype "bidirectional"))
      (node (ref "U5") (pin "1") (pinfunction "CS_1") (pintype "input"))
    )
    (net (code "128") (name "SW0") (class "Default")
      (node (ref "S1") (pin "1") (pinfunction "1_1") (pintype "passive"))
      (node (ref "S1") (pin "2") (pinfunction "2_2") (pintype "passive"))
      (node (ref "U$5") (pin "2") (pinfunction "PF0/OSC_IN_2") (pintype "bidirectional"))
    )
    (net (code "129") (name "SW1") (class "Default")
      (node (ref "S2") (pin "1") (pinfunction "1_1") (pintype "passive"))
      (node (ref "S2") (pin "2") (pinfunction "2_2") (pintype "passive"))
      (node (ref "U$5") (pin "3") (pinfunction "PF1/OSC_OUT_3") (pintype "bidirectional"))
    )
    (net (code "130") (name "SW2") (class "Default")
      (node (ref "S3") (pin "1") (pinfunction "1_1") (pintype "passive"))
      (node (ref "S3") (pin "2") (pinfunction "2_2") (pintype "passive"))
      (node (ref "U2") (pin "14") (pinfunction "PA4_14") (pintype "bidirectional"))
    )
    (net (code "131") (name "SW3") (class "Default")
      (node (ref "S4") (pin "1") (pinfunction "1_1") (pintype "passive"))
      (node (ref "S4") (pin "2") (pinfunction "2_2") (pintype "passive"))
      (node (ref "U2") (pin "19") (pinfunction "PB1_19") (pintype "bidirectional"))
    )
    (net (code "132") (name "SWDCLK") (class "Default")
      (node (ref "JP2") (pin "2") (pinfunction "2_2") (pintype "passive"))
      (node (ref "U2") (pin "37") (pinfunction "PA14_37") (pintype "bidirectional"))
    )
    (net (code "133") (name "SWDIO") (class "Default")
      (node (ref "JP2") (pin "3") (pinfunction "3_3") (pintype "passive"))
      (node (ref "U2") (pin "34") (pinfunction "PA13_34") (pintype "bidirectional"))
    )
    (net (code "134") (name "TX1+") (class "Default")
      (node (ref "J2") (pin "1") (pinfunction "TD+_1") (pintype "bidirectional"))
      (node (ref "R12") (pin "1") (pinfunction "1_1") (pintype "passive"))
      (node (ref "U$1") (pin "20") (pinfunction "TPOUT+_20") (pintype "bidirectional"))
    )
    (net (code "135") (name "TX1-") (class "Default")
      (node (ref "J2") (pin "3") (pinfunction "TD-_3") (pintype "bidirectional"))
      (node (ref "R13") (pin "1") (pinfunction "1_1") (pintype "passive"))
      (node (ref "U$1") (pin "21") (pinfunction "TPOUT-_21") (pintype "bidirectional"))
    )
    (net (code "136") (name "TX1_CT") (class "Default")
      (node (ref "C29") (pin "1") (pinfunction "1_1") (pintype "passive"))
      (node (ref "J2") (pin "2") (pinfunction "TXCT_2") (pintype "bidirectional"))
      (node (ref "R16") (pin "1") (pinfunction "1_1") (pintype "passive"))
    )
    (net (code "137") (name "TX2+") (class "Default")
      (node (ref "J3") (pin "1") (pinfunction "TD+_1") (pintype "bidirectional"))
      (node (ref "R21") (pin "1") (pinfunction "1_1") (pintype "passive"))
      (node (ref "U$3") (pin "20") (pinfunction "TPOUT+_20") (pintype "bidirectional"))
    )
    (net (code "138") (name "TX2-") (class "Default")
      (node (ref "J3") (pin "3") (pinfunction "TD-_3") (pintype "bidirectional"))
      (node (ref "R22") (pin "1") (pinfunction "1_1") (pintype "passive"))
      (node (ref "U$3") (pin "21") (pinfunction "TPOUT-_21") (pintype "bidirectional"))
    )
    (net (code "139") (name "TX2_CT") (class "Default")
      (node (ref "C41") (pin "1") (pinfunction "1_1") (pintype "passive"))
      (node (ref "J3") (pin "2") (pinfunction "TXCT_2") (pintype "bidirectional"))
      (node (ref "R25") (pin "1") (pinfunction "1_1") (pintype "passive"))
    )
    (net (code "140") (name "UART_RX1") (class "Default")
      (node (ref "JP6") (pin "1") (pinfunction "1_1") (pintype "passive"))
      (node (ref "U2") (pin "22") (pinfunction "PB11_22") (pintype "bidirectional"))
    )
    (net (code "141") (name "UART_RX2") (class "Default")
      (node (ref "JP7") (pin "2") (pinfunction "2_2") (pintype "passive"))
      (node (ref "U2") (pin "31") (pinfunction "PA10_31") (pintype "bidirectional"))
      (node (ref "U4") (pin "12") (pinfunction "R1OUT_12") (pintype "output"))
    )
    (net (code "142") (name "UART_TX1") (class "Default")
      (node (ref "JP6") (pin "2") (pinfunction "2_2") (pintype "passive"))
      (node (ref "U2") (pin "21") (pinfunction "PB10_21") (pintype "bidirectional"))
    )
    (net (code "143") (name "UART_TX2") (class "Default")
      (node (ref "JP7") (pin "3") (pinfunction "3_3") (pintype "passive"))
      (node (ref "U2") (pin "30") (pinfunction "PA9_30") (pintype "bidirectional"))
      (node (ref "U4") (pin "11") (pinfunction "T1IN_11") (pintype "input"))
    )
    (net (code "144") (name "USB_D+") (class "Default")
      (node (ref "R45") (pin "1") (pinfunction "1_1") (pintype "passive"))
      (node (ref "R6") (pin "1") (pinfunction "1_1") (pintype "passive"))
      (node (ref "U2") (pin "33") (pinfunction "PA12_33") (pintype "bidirectional"))
    )
    (net (code "145") (name "USB_D-") (class "Default")
      (node (ref "R5") (pin "1") (pinfunction "1_1") (pintype "passive"))
      (node (ref "U2") (pin "32") (pinfunction "PA11_32") (pintype "power_in"))
    )
    (net (code "146") (name "VBAT") (class "Default")
      (node (ref "D5") (pin "3") (pinfunction "C_3") (pintype "passive"))
      (node (ref "U2") (pin "1") (pinfunction "VBAT_1") (pintype "input"))
    )
    (net (code "147") (name "VIN") (class "Default")
      (node (ref "C15") (pin "+") (pinfunction "+_+") (pintype "passive"))
      (node (ref "D8") (pin "C") (pinfunction "C_C") (pintype "passive"))
      (node (ref "R7") (pin "2") (pinfunction "2_2") (pintype "passive"))
      (node (ref "U3") (pin "6") (pinfunction "VCC_6") (pintype "bidirectional"))
    )
    (net (code "148") (name "VIN2") (class "Default")
      (node (ref "R7") (pin "1") (pinfunction "1_1") (pintype "passive"))
      (node (ref "U3") (pin "1") (pinfunction "SWC_1") (pintype "bidirectional"))
      (node (ref "U3") (pin "7") (pinfunction "SEN_7") (pintype "bidirectional"))
      (node (ref "U3") (pin "8") (pinfunction "DVR_8") (pintype "bidirectional"))
    )
    (net (code "149") (name "unconnected-(IC5-DNC-Pad3)") (class "Default")
      (node (ref "IC5") (pin "3") (pinfunction "DNC_3") (pintype "no_connect"))
    )
    (net (code "150") (name "unconnected-(IC5-DNC-Pad4)") (class "Default")
      (node (ref "IC5") (pin "4") (pinfunction "DNC_4") (pintype "no_connect"))
    )
    (net (code "151") (name "unconnected-(J2-NC-Pad7)") (class "Default")
      (node (ref "J2") (pin "7") (pinfunction "NC_7") (pintype "bidirectional"))
    )
    (net (code "152") (name "unconnected-(J3-NC-Pad7)") (class "Default")
      (node (ref "J3") (pin "7") (pinfunction "NC_7") (pintype "bidirectional"))
    )
    (net (code "153") (name "unconnected-(JP3-PadVBUS)") (class "Default")
      (node (ref "JP3") (pin "VBUS") (pinfunction "VBUS_VBUS") (pintype "bidirectional"))
    )
    (net (code "154") (name "unconnected-(JP12-Pad4)") (class "Default")
      (node (ref "JP12") (pin "4") (pinfunction "4_4") (pintype "passive"))
    )
    (net (code "155") (name "unconnected-(JP12-Pad6)") (class "Default")
      (node (ref "JP12") (pin "6") (pinfunction "6_6") (pintype "passive"))
    )
    (net (code "156") (name "unconnected-(JP12-Pad9)") (class "Default")
      (node (ref "JP12") (pin "9") (pinfunction "9_9") (pintype "passive"))
    )
    (net (code "157") (name "unconnected-(JP12-Pad10)") (class "Default")
      (node (ref "JP12") (pin "10") (pinfunction "10_10") (pintype "passive"))
    )
    (net (code "158") (name "unconnected-(U$1-AD0-Pad38)") (class "Default")
      (node (ref "U$1") (pin "38") (pinfunction "AD0_38") (pintype "bidirectional"))
    )
    (net (code "159") (name "unconnected-(U$1-AD1-Pad39)") (class "Default")
      (node (ref "U$1") (pin "39") (pinfunction "AD1_39") (pintype "bidirectional"))
    )
    (net (code "160") (name "unconnected-(U$1-AD2-Pad40)") (class "Default")
      (node (ref "U$1") (pin "40") (pinfunction "AD2_40") (pintype "bidirectional"))
    )
    (net (code "161") (name "unconnected-(U$1-AD3-Pad41)") (class "Default")
      (node (ref "U$1") (pin "41") (pinfunction "AD3_41") (pintype "bidirectional"))
    )
    (net (code "162") (name "unconnected-(U$1-AD4-Pad5)") (class "Default")
      (node (ref "U$1") (pin "5") (pinfunction "AD4_5") (pintype "bidirectional"))
    )
    (net (code "163") (name "unconnected-(U$1-AD5-Pad6)") (class "Default")
      (node (ref "U$1") (pin "6") (pinfunction "AD5_6") (pintype "bidirectional"))
    )
    (net (code "164") (name "unconnected-(U$1-AD6-Pad7)") (class "Default")
      (node (ref "U$1") (pin "7") (pinfunction "AD6_7") (pintype "bidirectional"))
    )
    (net (code "165") (name "unconnected-(U$1-AD7-Pad8)") (class "Default")
      (node (ref "U$1") (pin "8") (pinfunction "AD7_8") (pintype "bidirectional"))
    )
    (net (code "166") (name "unconnected-(U$1-AD8-Pad25)") (class "Default")
      (node (ref "U$1") (pin "25") (pinfunction "AD8_25") (pintype "bidirectional"))
    )
    (net (code "167") (name "unconnected-(U$1-AD9-Pad26)") (class "Default")
      (node (ref "U$1") (pin "26") (pinfunction "AD9_26") (pintype "bidirectional"))
    )
    (net (code "168") (name "unconnected-(U$1-AD10-Pad27)") (class "Default")
      (node (ref "U$1") (pin "27") (pinfunction "AD10_27") (pintype "bidirectional"))
    )
    (net (code "169") (name "unconnected-(U$1-AD11-Pad28)") (class "Default")
      (node (ref "U$1") (pin "28") (pinfunction "AD11_28") (pintype "bidirectional"))
    )
    (net (code "170") (name "unconnected-(U$1-AD12-Pad29)") (class "Default")
      (node (ref "U$1") (pin "29") (pinfunction "AD12_29") (pintype "bidirectional"))
    )
    (net (code "171") (name "unconnected-(U$1-AD13-Pad30)") (class "Default")
      (node (ref "U$1") (pin "30") (pinfunction "AD13_30") (pintype "bidirectional"))
    )
    (net (code "172") (name "unconnected-(U$1-AD14-Pad31)") (class "Default")
      (node (ref "U$1") (pin "31") (pinfunction "AD14_31") (pintype "bidirectional"))
    )
    (net (code "173") (name "unconnected-(U$1-CLKOUT-Pad23)") (class "Default")
      (node (ref "U$1") (pin "23") (pinfunction "CLKOUT_23") (pintype "bidirectional"))
    )
    (net (code "174") (name "unconnected-(U$1-PSPCFG0-Pad32)") (class "Default")
      (node (ref "U$1") (pin "32") (pinfunction "PSPCFG0_32") (pintype "bidirectional"))
    )
    (net (code "175") (name "unconnected-(U$3-AD0-Pad38)") (class "Default")
      (node (ref "U$3") (pin "38") (pinfunction "AD0_38") (pintype "bidirectional"))
    )
    (net (code "176") (name "unconnected-(U$3-AD1-Pad39)") (class "Default")
      (node (ref "U$3") (pin "39") (pinfunction "AD1_39") (pintype "bidirectional"))
    )
    (net (code "177") (name "unconnected-(U$3-AD2-Pad40)") (class "Default")
      (node (ref "U$3") (pin "40") (pinfunction "AD2_40") (pintype "bidirectional"))
    )
    (net (code "178") (name "unconnected-(U$3-AD3-Pad41)") (class "Default")
      (node (ref "U$3") (pin "41") (pinfunction "AD3_41") (pintype "bidirectional"))
    )
    (net (code "179") (name "unconnected-(U$3-AD4-Pad5)") (class "Default")
      (node (ref "U$3") (pin "5") (pinfunction "AD4_5") (pintype "bidirectional"))
    )
    (net (code "180") (name "unconnected-(U$3-AD5-Pad6)") (class "Default")
      (node (ref "U$3") (pin "6") (pinfunction "AD5_6") (pintype "bidirectional"))
    )
    (net (code "181") (name "unconnected-(U$3-AD6-Pad7)") (class "Default")
      (node (ref "U$3") (pin "7") (pinfunction "AD6_7") (pintype "bidirectional"))
    )
    (net (code "182") (name "unconnected-(U$3-AD7-Pad8)") (class "Default")
      (node (ref "U$3") (pin "8") (pinfunction "AD7_8") (pintype "bidirectional"))
    )
    (net (code "183") (name "unconnected-(U$3-AD8-Pad25)") (class "Default")
      (node (ref "U$3") (pin "25") (pinfunction "AD8_25") (pintype "bidirectional"))
    )
    (net (code "184") (name "unconnected-(U$3-AD9-Pad26)") (class "Default")
      (node (ref "U$3") (pin "26") (pinfunction "AD9_26") (pintype "bidirectional"))
    )
    (net (code "185") (name "unconnected-(U$3-AD10-Pad27)") (class "Default")
      (node (ref "U$3") (pin "27") (pinfunction "AD10_27") (pintype "bidirectional"))
    )
    (net (code "186") (name "unconnected-(U$3-AD11-Pad28)") (class "Default")
      (node (ref "U$3") (pin "28") (pinfunction "AD11_28") (pintype "bidirectional"))
    )
    (net (code "187") (name "unconnected-(U$3-AD12-Pad29)") (class "Default")
      (node (ref "U$3") (pin "29") (pinfunction "AD12_29") (pintype "bidirectional"))
    )
    (net (code "188") (name "unconnected-(U$3-AD13-Pad30)") (class "Default")
      (node (ref "U$3") (pin "30") (pinfunction "AD13_30") (pintype "bidirectional"))
    )
    (net (code "189") (name "unconnected-(U$3-AD14-Pad31)") (class "Default")
      (node (ref "U$3") (pin "31") (pinfunction "AD14_31") (pintype "bidirectional"))
    )
    (net (code "190") (name "unconnected-(U$3-CLKOUT-Pad23)") (class "Default")
      (node (ref "U$3") (pin "23") (pinfunction "CLKOUT_23") (pintype "bidirectional"))
    )
    (net (code "191") (name "unconnected-(U$3-PSPCFG0-Pad32)") (class "Default")
      (node (ref "U$3") (pin "32") (pinfunction "PSPCFG0_32") (pintype "bidirectional"))
    )
    (net (code "192") (name "unconnected-(U$5-PA12-Pad22)") (class "Default")
      (node (ref "U$5") (pin "22") (pinfunction "PA12_22") (pintype "bidirectional"))
    )
    (net (code "193") (name "unconnected-(U2-PA0-WKUP-Pad10)") (class "Default")
      (node (ref "U2") (pin "10") (pinfunction "PA0-WKUP_10") (pintype "bidirectional"))
    )
    (net (code "194") (name "unconnected-(U2-PA1-Pad11)") (class "Default")
      (node (ref "U2") (pin "11") (pinfunction "PA1_11") (pintype "bidirectional"))
    )
    (net (code "195") (name "unconnected-(U2-PA15-Pad38)") (class "Default")
      (node (ref "U2") (pin "38") (pinfunction "PA15_38") (pintype "bidirectional"))
    )
    (net (code "196") (name "unconnected-(U2-PB2-Pad20)") (class "Default")
      (node (ref "U2") (pin "20") (pinfunction "PB2_20") (pintype "bidirectional"))
    )
    (net (code "197") (name "unconnected-(U2-PB3-Pad39)") (class "Default")
      (node (ref "U2") (pin "39") (pinfunction "PB3_39") (pintype "bidirectional"))
    )
    (net (code "198") (name "unconnected-(U2-PB4-Pad40)") (class "Default")
      (node (ref "U2") (pin "40") (pinfunction "PB4_40") (pintype "bidirectional"))
    )
    (net (code "199") (name "unconnected-(U2-PB5-Pad41)") (class "Default")
      (node (ref "U2") (pin "41") (pinfunction "PB5_41") (pintype "bidirectional"))
    )
    (net (code "200") (name "unconnected-(U2-PB8-Pad45)") (class "Default")
      (node (ref "U2") (pin "45") (pinfunction "PB8_45") (pintype "bidirectional"))
    )
    (net (code "201") (name "unconnected-(U2-PB9-Pad46)") (class "Default")
      (node (ref "U2") (pin "46") (pinfunction "PB9_46") (pintype "bidirectional"))
    )
    (net (code "202") (name "unconnected-(U2-PC13-TAMPER-RTC-Pad2)") (class "Default")
      (node (ref "U2") (pin "2") (pinfunction "PC13-TAMPER-RTC_2") (pintype "bidirectional"))
    )
    (net (code "203") (name "unconnected-(U4-R2IN-Pad8)") (class "Default")
      (node (ref "U4") (pin "8") (pinfunction "R2IN_8") (pintype "input"))
    )
    (net (code "204") (name "unconnected-(U4-R2OUT-Pad9)") (class "Default")
      (node (ref "U4") (pin "9") (pinfunction "R2OUT_9") (pintype "output"))
    )
    (net (code "205") (name "unconnected-(U4-T2IN-Pad10)") (class "Default")
      (node (ref "U4") (pin "10") (pinfunction "T2IN_10") (pintype "input"))
    )
    (net (code "206") (name "unconnected-(U4-T2OUT-Pad7)") (class "Default")
      (node (ref "U4") (pin "7") (pinfunction "T2OUT_7") (pintype "output"))
    )
    (net (code "207") (name "unconnected-(U5-HOLD_(IO3)-Pad7)") (class "Default")
      (node (ref "U5") (pin "7") (pinfunction "HOLD_(IO3)_7") (pintype "bidirectional"))
    )
    (net (code "208") (name "unconnected-(U5-WP_(IO2)-Pad3)") (class "Default")
      (node (ref "U5") (pin "3") (pinfunction "WP_(IO2)_3") (pintype "bidirectional"))
    )
    (net (code "209") (name "unconnected-(X1-Pad1)") (class "Default")
      (node (ref "X1") (pin "1") (pinfunction "1_1") (pintype "passive"))
    )
    (net (code "210") (name "unconnected-(X1-Pad4)") (class "Default")
      (node (ref "X1") (pin "4") (pinfunction "4_4") (pintype "passive"))
    )
    (net (code "211") (name "unconnected-(X1-Pad6)") (class "Default")
      (node (ref "X1") (pin "6") (pinfunction "6_6") (pintype "passive"))
    )
    (net (code "212") (name "unconnected-(X1-Pad7)") (class "Default")
      (node (ref "X1") (pin "7") (pinfunction "7_7") (pintype "passive"))
    )
    (net (code "213") (name "unconnected-(X1-Pad8)") (class "Default")
      (node (ref "X1") (pin "8") (pinfunction "8_8") (pintype "passive"))
    )
    (net (code "214") (name "unconnected-(X1-Pad9)") (class "Default")
      (node (ref "X1") (pin "9") (pinfunction "9_9") (pintype "passive"))
    )
  )
)
